# Matrix.net
KiCad netlist of a schematic drawn in Altium Designer
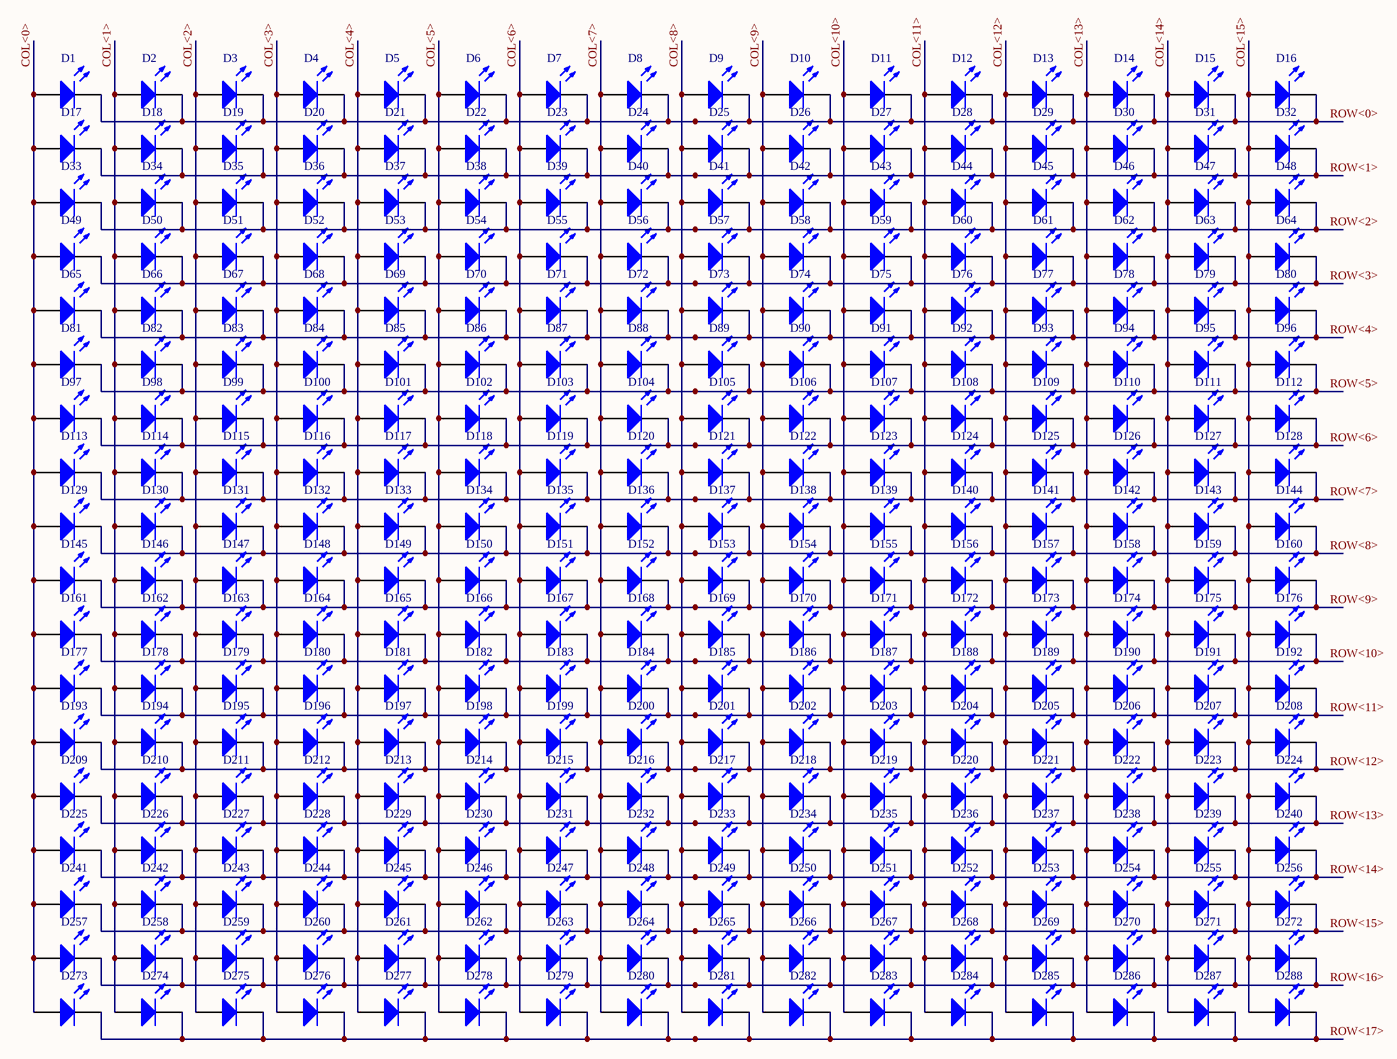
[diagram p0: Matrix.SchDoc]

(export (version "E")
  (design (tool "Eeschema 10.0.6"))
  (components
    (comp (ref "D1")
      (value "~")
      (footprint "LED-UPRIGHT")
      (description "Typical INFRARED GaAs LED")
      (fields (field (name "MANUFACTURER") "Generic Components") (field (name "PUBLISHER") "Altium Limited"))
      (libsource (lib "Miscellaneous Devices") (part "LED0"))
    )
    (comp (ref "D2")
      (value "~")
      (footprint "LED-UPRIGHT")
      (description "Typical INFRARED GaAs LED")
      (fields (field (name "MANUFACTURER") "Generic Components") (field (name "PUBLISHER") "Altium Limited"))
      (libsource (lib "Miscellaneous Devices") (part "LED0"))
    )
    (comp (ref "D3")
      (value "~")
      (footprint "LED-UPRIGHT")
      (description "Typical INFRARED GaAs LED")
      (fields (field (name "MANUFACTURER") "Generic Components") (field (name "PUBLISHER") "Altium Limited"))
      (libsource (lib "Miscellaneous Devices") (part "LED0"))
    )
    (comp (ref "D4")
      (value "~")
      (footprint "LED-UPRIGHT")
      (description "Typical INFRARED GaAs LED")
      (fields (field (name "MANUFACTURER") "Generic Components") (field (name "PUBLISHER") "Altium Limited"))
      (libsource (lib "Miscellaneous Devices") (part "LED0"))
    )
    (comp (ref "D5")
      (value "~")
      (footprint "LED-UPRIGHT")
      (description "Typical INFRARED GaAs LED")
      (fields (field (name "MANUFACTURER") "Generic Components") (field (name "PUBLISHER") "Altium Limited"))
      (libsource (lib "Miscellaneous Devices") (part "LED0"))
    )
    (comp (ref "D6")
      (value "~")
      (footprint "LED-UPRIGHT")
      (description "Typical INFRARED GaAs LED")
      (fields (field (name "MANUFACTURER") "Generic Components") (field (name "PUBLISHER") "Altium Limited"))
      (libsource (lib "Miscellaneous Devices") (part "LED0"))
    )
    (comp (ref "D7")
      (value "~")
      (footprint "LED-UPRIGHT")
      (description "Typical INFRARED GaAs LED")
      (fields (field (name "MANUFACTURER") "Generic Components") (field (name "PUBLISHER") "Altium Limited"))
      (libsource (lib "Miscellaneous Devices") (part "LED0"))
    )
    (comp (ref "D8")
      (value "~")
      (footprint "LED-UPRIGHT")
      (description "Typical INFRARED GaAs LED")
      (fields (field (name "MANUFACTURER") "Generic Components") (field (name "PUBLISHER") "Altium Limited"))
      (libsource (lib "Miscellaneous Devices") (part "LED0"))
    )
    (comp (ref "D9")
      (value "~")
      (footprint "LED-UPRIGHT")
      (description "Typical INFRARED GaAs LED")
      (fields (field (name "MANUFACTURER") "Generic Components") (field (name "PUBLISHER") "Altium Limited"))
      (libsource (lib "Miscellaneous Devices") (part "LED0"))
    )
    (comp (ref "D10")
      (value "~")
      (footprint "LED-UPRIGHT")
      (description "Typical INFRARED GaAs LED")
      (fields (field (name "MANUFACTURER") "Generic Components") (field (name "PUBLISHER") "Altium Limited"))
      (libsource (lib "Miscellaneous Devices") (part "LED0"))
    )
    (comp (ref "D11")
      (value "~")
      (footprint "LED-UPRIGHT")
      (description "Typical INFRARED GaAs LED")
      (fields (field (name "MANUFACTURER") "Generic Components") (field (name "PUBLISHER") "Altium Limited"))
      (libsource (lib "Miscellaneous Devices") (part "LED0"))
    )
    (comp (ref "D12")
      (value "~")
      (footprint "LED-UPRIGHT")
      (description "Typical INFRARED GaAs LED")
      (fields (field (name "MANUFACTURER") "Generic Components") (field (name "PUBLISHER") "Altium Limited"))
      (libsource (lib "Miscellaneous Devices") (part "LED0"))
    )
    (comp (ref "D13")
      (value "~")
      (footprint "LED-UPRIGHT")
      (description "Typical INFRARED GaAs LED")
      (fields (field (name "MANUFACTURER") "Generic Components") (field (name "PUBLISHER") "Altium Limited"))
      (libsource (lib "Miscellaneous Devices") (part "LED0"))
    )
    (comp (ref "D14")
      (value "~")
      (footprint "LED-UPRIGHT")
      (description "Typical INFRARED GaAs LED")
      (fields (field (name "MANUFACTURER") "Generic Components") (field (name "PUBLISHER") "Altium Limited"))
      (libsource (lib "Miscellaneous Devices") (part "LED0"))
    )
    (comp (ref "D15")
      (value "~")
      (footprint "LED-UPRIGHT")
      (description "Typical INFRARED GaAs LED")
      (fields (field (name "MANUFACTURER") "Generic Components") (field (name "PUBLISHER") "Altium Limited"))
      (libsource (lib "Miscellaneous Devices") (part "LED0"))
    )
    (comp (ref "D16")
      (value "~")
      (footprint "LED-UPRIGHT")
      (description "Typical INFRARED GaAs LED")
      (fields (field (name "MANUFACTURER") "Generic Components") (field (name "PUBLISHER") "Altium Limited"))
      (libsource (lib "Miscellaneous Devices") (part "LED0"))
    )
    (comp (ref "D17")
      (value "~")
      (footprint "LED-UPRIGHT")
      (description "Typical INFRARED GaAs LED")
      (fields (field (name "MANUFACTURER") "Generic Components") (field (name "PUBLISHER") "Altium Limited"))
      (libsource (lib "Miscellaneous Devices") (part "LED0"))
    )
    (comp (ref "D18")
      (value "~")
      (footprint "LED-UPRIGHT")
      (description "Typical INFRARED GaAs LED")
      (fields (field (name "MANUFACTURER") "Generic Components") (field (name "PUBLISHER") "Altium Limited"))
      (libsource (lib "Miscellaneous Devices") (part "LED0"))
    )
    (comp (ref "D19")
      (value "~")
      (footprint "LED-UPRIGHT")
      (description "Typical INFRARED GaAs LED")
      (fields (field (name "MANUFACTURER") "Generic Components") (field (name "PUBLISHER") "Altium Limited"))
      (libsource (lib "Miscellaneous Devices") (part "LED0"))
    )
    (comp (ref "D20")
      (value "~")
      (footprint "LED-UPRIGHT")
      (description "Typical INFRARED GaAs LED")
      (fields (field (name "MANUFACTURER") "Generic Components") (field (name "PUBLISHER") "Altium Limited"))
      (libsource (lib "Miscellaneous Devices") (part "LED0"))
    )
    (comp (ref "D21")
      (value "~")
      (footprint "LED-UPRIGHT")
      (description "Typical INFRARED GaAs LED")
      (fields (field (name "MANUFACTURER") "Generic Components") (field (name "PUBLISHER") "Altium Limited"))
      (libsource (lib "Miscellaneous Devices") (part "LED0"))
    )
    (comp (ref "D22")
      (value "~")
      (footprint "LED-UPRIGHT")
      (description "Typical INFRARED GaAs LED")
      (fields (field (name "MANUFACTURER") "Generic Components") (field (name "PUBLISHER") "Altium Limited"))
      (libsource (lib "Miscellaneous Devices") (part "LED0"))
    )
    (comp (ref "D23")
      (value "~")
      (footprint "LED-UPRIGHT")
      (description "Typical INFRARED GaAs LED")
      (fields (field (name "MANUFACTURER") "Generic Components") (field (name "PUBLISHER") "Altium Limited"))
      (libsource (lib "Miscellaneous Devices") (part "LED0"))
    )
    (comp (ref "D24")
      (value "~")
      (footprint "LED-UPRIGHT")
      (description "Typical INFRARED GaAs LED")
      (fields (field (name "MANUFACTURER") "Generic Components") (field (name "PUBLISHER") "Altium Limited"))
      (libsource (lib "Miscellaneous Devices") (part "LED0"))
    )
    (comp (ref "D25")
      (value "~")
      (footprint "LED-UPRIGHT")
      (description "Typical INFRARED GaAs LED")
      (fields (field (name "MANUFACTURER") "Generic Components") (field (name "PUBLISHER") "Altium Limited"))
      (libsource (lib "Miscellaneous Devices") (part "LED0"))
    )
    (comp (ref "D26")
      (value "~")
      (footprint "LED-UPRIGHT")
      (description "Typical INFRARED GaAs LED")
      (fields (field (name "MANUFACTURER") "Generic Components") (field (name "PUBLISHER") "Altium Limited"))
      (libsource (lib "Miscellaneous Devices") (part "LED0"))
    )
    (comp (ref "D27")
      (value "~")
      (footprint "LED-UPRIGHT")
      (description "Typical INFRARED GaAs LED")
      (fields (field (name "MANUFACTURER") "Generic Components") (field (name "PUBLISHER") "Altium Limited"))
      (libsource (lib "Miscellaneous Devices") (part "LED0"))
    )
    (comp (ref "D28")
      (value "~")
      (footprint "LED-UPRIGHT")
      (description "Typical INFRARED GaAs LED")
      (fields (field (name "MANUFACTURER") "Generic Components") (field (name "PUBLISHER") "Altium Limited"))
      (libsource (lib "Miscellaneous Devices") (part "LED0"))
    )
    (comp (ref "D29")
      (value "~")
      (footprint "LED-UPRIGHT")
      (description "Typical INFRARED GaAs LED")
      (fields (field (name "MANUFACTURER") "Generic Components") (field (name "PUBLISHER") "Altium Limited"))
      (libsource (lib "Miscellaneous Devices") (part "LED0"))
    )
    (comp (ref "D30")
      (value "~")
      (footprint "LED-UPRIGHT")
      (description "Typical INFRARED GaAs LED")
      (fields (field (name "MANUFACTURER") "Generic Components") (field (name "PUBLISHER") "Altium Limited"))
      (libsource (lib "Miscellaneous Devices") (part "LED0"))
    )
    (comp (ref "D31")
      (value "~")
      (footprint "LED-UPRIGHT")
      (description "Typical INFRARED GaAs LED")
      (fields (field (name "MANUFACTURER") "Generic Components") (field (name "PUBLISHER") "Altium Limited"))
      (libsource (lib "Miscellaneous Devices") (part "LED0"))
    )
    (comp (ref "D32")
      (value "~")
      (footprint "LED-UPRIGHT")
      (description "Typical INFRARED GaAs LED")
      (fields (field (name "MANUFACTURER") "Generic Components") (field (name "PUBLISHER") "Altium Limited"))
      (libsource (lib "Miscellaneous Devices") (part "LED0"))
    )
    (comp (ref "D33")
      (value "~")
      (footprint "LED-UPRIGHT")
      (description "Typical INFRARED GaAs LED")
      (fields (field (name "MANUFACTURER") "Generic Components") (field (name "PUBLISHER") "Altium Limited"))
      (libsource (lib "Miscellaneous Devices") (part "LED0"))
    )
    (comp (ref "D34")
      (value "~")
      (footprint "LED-UPRIGHT")
      (description "Typical INFRARED GaAs LED")
      (fields (field (name "MANUFACTURER") "Generic Components") (field (name "PUBLISHER") "Altium Limited"))
      (libsource (lib "Miscellaneous Devices") (part "LED0"))
    )
    (comp (ref "D35")
      (value "~")
      (footprint "LED-UPRIGHT")
      (description "Typical INFRARED GaAs LED")
      (fields (field (name "MANUFACTURER") "Generic Components") (field (name "PUBLISHER") "Altium Limited"))
      (libsource (lib "Miscellaneous Devices") (part "LED0"))
    )
    (comp (ref "D36")
      (value "~")
      (footprint "LED-UPRIGHT")
      (description "Typical INFRARED GaAs LED")
      (fields (field (name "MANUFACTURER") "Generic Components") (field (name "PUBLISHER") "Altium Limited"))
      (libsource (lib "Miscellaneous Devices") (part "LED0"))
    )
    (comp (ref "D37")
      (value "~")
      (footprint "LED-UPRIGHT")
      (description "Typical INFRARED GaAs LED")
      (fields (field (name "MANUFACTURER") "Generic Components") (field (name "PUBLISHER") "Altium Limited"))
      (libsource (lib "Miscellaneous Devices") (part "LED0"))
    )
    (comp (ref "D38")
      (value "~")
      (footprint "LED-UPRIGHT")
      (description "Typical INFRARED GaAs LED")
      (fields (field (name "MANUFACTURER") "Generic Components") (field (name "PUBLISHER") "Altium Limited"))
      (libsource (lib "Miscellaneous Devices") (part "LED0"))
    )
    (comp (ref "D39")
      (value "~")
      (footprint "LED-UPRIGHT")
      (description "Typical INFRARED GaAs LED")
      (fields (field (name "MANUFACTURER") "Generic Components") (field (name "PUBLISHER") "Altium Limited"))
      (libsource (lib "Miscellaneous Devices") (part "LED0"))
    )
    (comp (ref "D40")
      (value "~")
      (footprint "LED-UPRIGHT")
      (description "Typical INFRARED GaAs LED")
      (fields (field (name "MANUFACTURER") "Generic Components") (field (name "PUBLISHER") "Altium Limited"))
      (libsource (lib "Miscellaneous Devices") (part "LED0"))
    )
    (comp (ref "D41")
      (value "~")
      (footprint "LED-UPRIGHT")
      (description "Typical INFRARED GaAs LED")
      (fields (field (name "MANUFACTURER") "Generic Components") (field (name "PUBLISHER") "Altium Limited"))
      (libsource (lib "Miscellaneous Devices") (part "LED0"))
    )
    (comp (ref "D42")
      (value "~")
      (footprint "LED-UPRIGHT")
      (description "Typical INFRARED GaAs LED")
      (fields (field (name "MANUFACTURER") "Generic Components") (field (name "PUBLISHER") "Altium Limited"))
      (libsource (lib "Miscellaneous Devices") (part "LED0"))
    )
    (comp (ref "D43")
      (value "~")
      (footprint "LED-UPRIGHT")
      (description "Typical INFRARED GaAs LED")
      (fields (field (name "MANUFACTURER") "Generic Components") (field (name "PUBLISHER") "Altium Limited"))
      (libsource (lib "Miscellaneous Devices") (part "LED0"))
    )
    (comp (ref "D44")
      (value "~")
      (footprint "LED-UPRIGHT")
      (description "Typical INFRARED GaAs LED")
      (fields (field (name "MANUFACTURER") "Generic Components") (field (name "PUBLISHER") "Altium Limited"))
      (libsource (lib "Miscellaneous Devices") (part "LED0"))
    )
    (comp (ref "D45")
      (value "~")
      (footprint "LED-UPRIGHT")
      (description "Typical INFRARED GaAs LED")
      (fields (field (name "MANUFACTURER") "Generic Components") (field (name "PUBLISHER") "Altium Limited"))
      (libsource (lib "Miscellaneous Devices") (part "LED0"))
    )
    (comp (ref "D46")
      (value "~")
      (footprint "LED-UPRIGHT")
      (description "Typical INFRARED GaAs LED")
      (fields (field (name "MANUFACTURER") "Generic Components") (field (name "PUBLISHER") "Altium Limited"))
      (libsource (lib "Miscellaneous Devices") (part "LED0"))
    )
    (comp (ref "D47")
      (value "~")
      (footprint "LED-UPRIGHT")
      (description "Typical INFRARED GaAs LED")
      (fields (field (name "MANUFACTURER") "Generic Components") (field (name "PUBLISHER") "Altium Limited"))
      (libsource (lib "Miscellaneous Devices") (part "LED0"))
    )
    (comp (ref "D48")
      (value "~")
      (footprint "LED-UPRIGHT")
      (description "Typical INFRARED GaAs LED")
      (fields (field (name "MANUFACTURER") "Generic Components") (field (name "PUBLISHER") "Altium Limited"))
      (libsource (lib "Miscellaneous Devices") (part "LED0"))
    )
    (comp (ref "D49")
      (value "~")
      (footprint "LED-UPRIGHT")
      (description "Typical INFRARED GaAs LED")
      (fields (field (name "MANUFACTURER") "Generic Components") (field (name "PUBLISHER") "Altium Limited"))
      (libsource (lib "Miscellaneous Devices") (part "LED0"))
    )
    (comp (ref "D50")
      (value "~")
      (footprint "LED-UPRIGHT")
      (description "Typical INFRARED GaAs LED")
      (fields (field (name "MANUFACTURER") "Generic Components") (field (name "PUBLISHER") "Altium Limited"))
      (libsource (lib "Miscellaneous Devices") (part "LED0"))
    )
    (comp (ref "D51")
      (value "~")
      (footprint "LED-UPRIGHT")
      (description "Typical INFRARED GaAs LED")
      (fields (field (name "MANUFACTURER") "Generic Components") (field (name "PUBLISHER") "Altium Limited"))
      (libsource (lib "Miscellaneous Devices") (part "LED0"))
    )
    (comp (ref "D52")
      (value "~")
      (footprint "LED-UPRIGHT")
      (description "Typical INFRARED GaAs LED")
      (fields (field (name "MANUFACTURER") "Generic Components") (field (name "PUBLISHER") "Altium Limited"))
      (libsource (lib "Miscellaneous Devices") (part "LED0"))
    )
    (comp (ref "D53")
      (value "~")
      (footprint "LED-UPRIGHT")
      (description "Typical INFRARED GaAs LED")
      (fields (field (name "MANUFACTURER") "Generic Components") (field (name "PUBLISHER") "Altium Limited"))
      (libsource (lib "Miscellaneous Devices") (part "LED0"))
    )
    (comp (ref "D54")
      (value "~")
      (footprint "LED-UPRIGHT")
      (description "Typical INFRARED GaAs LED")
      (fields (field (name "MANUFACTURER") "Generic Components") (field (name "PUBLISHER") "Altium Limited"))
      (libsource (lib "Miscellaneous Devices") (part "LED0"))
    )
    (comp (ref "D55")
      (value "~")
      (footprint "LED-UPRIGHT")
      (description "Typical INFRARED GaAs LED")
      (fields (field (name "MANUFACTURER") "Generic Components") (field (name "PUBLISHER") "Altium Limited"))
      (libsource (lib "Miscellaneous Devices") (part "LED0"))
    )
    (comp (ref "D56")
      (value "~")
      (footprint "LED-UPRIGHT")
      (description "Typical INFRARED GaAs LED")
      (fields (field (name "MANUFACTURER") "Generic Components") (field (name "PUBLISHER") "Altium Limited"))
      (libsource (lib "Miscellaneous Devices") (part "LED0"))
    )
    (comp (ref "D57")
      (value "~")
      (footprint "LED-UPRIGHT")
      (description "Typical INFRARED GaAs LED")
      (fields (field (name "MANUFACTURER") "Generic Components") (field (name "PUBLISHER") "Altium Limited"))
      (libsource (lib "Miscellaneous Devices") (part "LED0"))
    )
    (comp (ref "D58")
      (value "~")
      (footprint "LED-UPRIGHT")
      (description "Typical INFRARED GaAs LED")
      (fields (field (name "MANUFACTURER") "Generic Components") (field (name "PUBLISHER") "Altium Limited"))
      (libsource (lib "Miscellaneous Devices") (part "LED0"))
    )
    (comp (ref "D59")
      (value "~")
      (footprint "LED-UPRIGHT")
      (description "Typical INFRARED GaAs LED")
      (fields (field (name "MANUFACTURER") "Generic Components") (field (name "PUBLISHER") "Altium Limited"))
      (libsource (lib "Miscellaneous Devices") (part "LED0"))
    )
    (comp (ref "D60")
      (value "~")
      (footprint "LED-UPRIGHT")
      (description "Typical INFRARED GaAs LED")
      (fields (field (name "MANUFACTURER") "Generic Components") (field (name "PUBLISHER") "Altium Limited"))
      (libsource (lib "Miscellaneous Devices") (part "LED0"))
    )
    (comp (ref "D61")
      (value "~")
      (footprint "LED-UPRIGHT")
      (description "Typical INFRARED GaAs LED")
      (fields (field (name "MANUFACTURER") "Generic Components") (field (name "PUBLISHER") "Altium Limited"))
      (libsource (lib "Miscellaneous Devices") (part "LED0"))
    )
    (comp (ref "D62")
      (value "~")
      (footprint "LED-UPRIGHT")
      (description "Typical INFRARED GaAs LED")
      (fields (field (name "MANUFACTURER") "Generic Components") (field (name "PUBLISHER") "Altium Limited"))
      (libsource (lib "Miscellaneous Devices") (part "LED0"))
    )
    (comp (ref "D63")
      (value "~")
      (footprint "LED-UPRIGHT")
      (description "Typical INFRARED GaAs LED")
      (fields (field (name "MANUFACTURER") "Generic Components") (field (name "PUBLISHER") "Altium Limited"))
      (libsource (lib "Miscellaneous Devices") (part "LED0"))
    )
    (comp (ref "D64")
      (value "~")
      (footprint "LED-UPRIGHT")
      (description "Typical INFRARED GaAs LED")
      (fields (field (name "MANUFACTURER") "Generic Components") (field (name "PUBLISHER") "Altium Limited"))
      (libsource (lib "Miscellaneous Devices") (part "LED0"))
    )
    (comp (ref "D65")
      (value "~")
      (footprint "LED-UPRIGHT")
      (description "Typical INFRARED GaAs LED")
      (fields (field (name "MANUFACTURER") "Generic Components") (field (name "PUBLISHER") "Altium Limited"))
      (libsource (lib "Miscellaneous Devices") (part "LED0"))
    )
    (comp (ref "D66")
      (value "~")
      (footprint "LED-UPRIGHT")
      (description "Typical INFRARED GaAs LED")
      (fields (field (name "MANUFACTURER") "Generic Components") (field (name "PUBLISHER") "Altium Limited"))
      (libsource (lib "Miscellaneous Devices") (part "LED0"))
    )
    (comp (ref "D67")
      (value "~")
      (footprint "LED-UPRIGHT")
      (description "Typical INFRARED GaAs LED")
      (fields (field (name "MANUFACTURER") "Generic Components") (field (name "PUBLISHER") "Altium Limited"))
      (libsource (lib "Miscellaneous Devices") (part "LED0"))
    )
    (comp (ref "D68")
      (value "~")
      (footprint "LED-UPRIGHT")
      (description "Typical INFRARED GaAs LED")
      (fields (field (name "MANUFACTURER") "Generic Components") (field (name "PUBLISHER") "Altium Limited"))
      (libsource (lib "Miscellaneous Devices") (part "LED0"))
    )
    (comp (ref "D69")
      (value "~")
      (footprint "LED-UPRIGHT")
      (description "Typical INFRARED GaAs LED")
      (fields (field (name "MANUFACTURER") "Generic Components") (field (name "PUBLISHER") "Altium Limited"))
      (libsource (lib "Miscellaneous Devices") (part "LED0"))
    )
    (comp (ref "D70")
      (value "~")
      (footprint "LED-UPRIGHT")
      (description "Typical INFRARED GaAs LED")
      (fields (field (name "MANUFACTURER") "Generic Components") (field (name "PUBLISHER") "Altium Limited"))
      (libsource (lib "Miscellaneous Devices") (part "LED0"))
    )
    (comp (ref "D71")
      (value "~")
      (footprint "LED-UPRIGHT")
      (description "Typical INFRARED GaAs LED")
      (fields (field (name "MANUFACTURER") "Generic Components") (field (name "PUBLISHER") "Altium Limited"))
      (libsource (lib "Miscellaneous Devices") (part "LED0"))
    )
    (comp (ref "D72")
      (value "~")
      (footprint "LED-UPRIGHT")
      (description "Typical INFRARED GaAs LED")
      (fields (field (name "MANUFACTURER") "Generic Components") (field (name "PUBLISHER") "Altium Limited"))
      (libsource (lib "Miscellaneous Devices") (part "LED0"))
    )
    (comp (ref "D73")
      (value "~")
      (footprint "LED-UPRIGHT")
      (description "Typical INFRARED GaAs LED")
      (fields (field (name "MANUFACTURER") "Generic Components") (field (name "PUBLISHER") "Altium Limited"))
      (libsource (lib "Miscellaneous Devices") (part "LED0"))
    )
    (comp (ref "D74")
      (value "~")
      (footprint "LED-UPRIGHT")
      (description "Typical INFRARED GaAs LED")
      (fields (field (name "MANUFACTURER") "Generic Components") (field (name "PUBLISHER") "Altium Limited"))
      (libsource (lib "Miscellaneous Devices") (part "LED0"))
    )
    (comp (ref "D75")
      (value "~")
      (footprint "LED-UPRIGHT")
      (description "Typical INFRARED GaAs LED")
      (fields (field (name "MANUFACTURER") "Generic Components") (field (name "PUBLISHER") "Altium Limited"))
      (libsource (lib "Miscellaneous Devices") (part "LED0"))
    )
    (comp (ref "D76")
      (value "~")
      (footprint "LED-UPRIGHT")
      (description "Typical INFRARED GaAs LED")
      (fields (field (name "MANUFACTURER") "Generic Components") (field (name "PUBLISHER") "Altium Limited"))
      (libsource (lib "Miscellaneous Devices") (part "LED0"))
    )
    (comp (ref "D77")
      (value "~")
      (footprint "LED-UPRIGHT")
      (description "Typical INFRARED GaAs LED")
      (fields (field (name "MANUFACTURER") "Generic Components") (field (name "PUBLISHER") "Altium Limited"))
      (libsource (lib "Miscellaneous Devices") (part "LED0"))
    )
    (comp (ref "D78")
      (value "~")
      (footprint "LED-UPRIGHT")
      (description "Typical INFRARED GaAs LED")
      (fields (field (name "MANUFACTURER") "Generic Components") (field (name "PUBLISHER") "Altium Limited"))
      (libsource (lib "Miscellaneous Devices") (part "LED0"))
    )
    (comp (ref "D79")
      (value "~")
      (footprint "LED-UPRIGHT")
      (description "Typical INFRARED GaAs LED")
      (fields (field (name "MANUFACTURER") "Generic Components") (field (name "PUBLISHER") "Altium Limited"))
      (libsource (lib "Miscellaneous Devices") (part "LED0"))
    )
    (comp (ref "D80")
      (value "~")
      (footprint "LED-UPRIGHT")
      (description "Typical INFRARED GaAs LED")
      (fields (field (name "MANUFACTURER") "Generic Components") (field (name "PUBLISHER") "Altium Limited"))
      (libsource (lib "Miscellaneous Devices") (part "LED0"))
    )
    (comp (ref "D81")
      (value "~")
      (footprint "LED-UPRIGHT")
      (description "Typical INFRARED GaAs LED")
      (fields (field (name "MANUFACTURER") "Generic Components") (field (name "PUBLISHER") "Altium Limited"))
      (libsource (lib "Miscellaneous Devices") (part "LED0"))
    )
    (comp (ref "D82")
      (value "~")
      (footprint "LED-UPRIGHT")
      (description "Typical INFRARED GaAs LED")
      (fields (field (name "MANUFACTURER") "Generic Components") (field (name "PUBLISHER") "Altium Limited"))
      (libsource (lib "Miscellaneous Devices") (part "LED0"))
    )
    (comp (ref "D83")
      (value "~")
      (footprint "LED-UPRIGHT")
      (description "Typical INFRARED GaAs LED")
      (fields (field (name "MANUFACTURER") "Generic Components") (field (name "PUBLISHER") "Altium Limited"))
      (libsource (lib "Miscellaneous Devices") (part "LED0"))
    )
    (comp (ref "D84")
      (value "~")
      (footprint "LED-UPRIGHT")
      (description "Typical INFRARED GaAs LED")
      (fields (field (name "MANUFACTURER") "Generic Components") (field (name "PUBLISHER") "Altium Limited"))
      (libsource (lib "Miscellaneous Devices") (part "LED0"))
    )
    (comp (ref "D85")
      (value "~")
      (footprint "LED-UPRIGHT")
      (description "Typical INFRARED GaAs LED")
      (fields (field (name "MANUFACTURER") "Generic Components") (field (name "PUBLISHER") "Altium Limited"))
      (libsource (lib "Miscellaneous Devices") (part "LED0"))
    )
    (comp (ref "D86")
      (value "~")
      (footprint "LED-UPRIGHT")
      (description "Typical INFRARED GaAs LED")
      (fields (field (name "MANUFACTURER") "Generic Components") (field (name "PUBLISHER") "Altium Limited"))
      (libsource (lib "Miscellaneous Devices") (part "LED0"))
    )
    (comp (ref "D87")
      (value "~")
      (footprint "LED-UPRIGHT")
      (description "Typical INFRARED GaAs LED")
      (fields (field (name "MANUFACTURER") "Generic Components") (field (name "PUBLISHER") "Altium Limited"))
      (libsource (lib "Miscellaneous Devices") (part "LED0"))
    )
    (comp (ref "D88")
      (value "~")
      (footprint "LED-UPRIGHT")
      (description "Typical INFRARED GaAs LED")
      (fields (field (name "MANUFACTURER") "Generic Components") (field (name "PUBLISHER") "Altium Limited"))
      (libsource (lib "Miscellaneous Devices") (part "LED0"))
    )
    (comp (ref "D89")
      (value "~")
      (footprint "LED-UPRIGHT")
      (description "Typical INFRARED GaAs LED")
      (fields (field (name "MANUFACTURER") "Generic Components") (field (name "PUBLISHER") "Altium Limited"))
      (libsource (lib "Miscellaneous Devices") (part "LED0"))
    )
    (comp (ref "D90")
      (value "~")
      (footprint "LED-UPRIGHT")
      (description "Typical INFRARED GaAs LED")
      (fields (field (name "MANUFACTURER") "Generic Components") (field (name "PUBLISHER") "Altium Limited"))
      (libsource (lib "Miscellaneous Devices") (part "LED0"))
    )
    (comp (ref "D91")
      (value "~")
      (footprint "LED-UPRIGHT")
      (description "Typical INFRARED GaAs LED")
      (fields (field (name "MANUFACTURER") "Generic Components") (field (name "PUBLISHER") "Altium Limited"))
      (libsource (lib "Miscellaneous Devices") (part "LED0"))
    )
    (comp (ref "D92")
      (value "~")
      (footprint "LED-UPRIGHT")
      (description "Typical INFRARED GaAs LED")
      (fields (field (name "MANUFACTURER") "Generic Components") (field (name "PUBLISHER") "Altium Limited"))
      (libsource (lib "Miscellaneous Devices") (part "LED0"))
    )
    (comp (ref "D93")
      (value "~")
      (footprint "LED-UPRIGHT")
      (description "Typical INFRARED GaAs LED")
      (fields (field (name "MANUFACTURER") "Generic Components") (field (name "PUBLISHER") "Altium Limited"))
      (libsource (lib "Miscellaneous Devices") (part "LED0"))
    )
    (comp (ref "D94")
      (value "~")
      (footprint "LED-UPRIGHT")
      (description "Typical INFRARED GaAs LED")
      (fields (field (name "MANUFACTURER") "Generic Components") (field (name "PUBLISHER") "Altium Limited"))
      (libsource (lib "Miscellaneous Devices") (part "LED0"))
    )
    (comp (ref "D95")
      (value "~")
      (footprint "LED-UPRIGHT")
      (description "Typical INFRARED GaAs LED")
      (fields (field (name "MANUFACTURER") "Generic Components") (field (name "PUBLISHER") "Altium Limited"))
      (libsource (lib "Miscellaneous Devices") (part "LED0"))
    )
    (comp (ref "D96")
      (value "~")
      (footprint "LED-UPRIGHT")
      (description "Typical INFRARED GaAs LED")
      (fields (field (name "MANUFACTURER") "Generic Components") (field (name "PUBLISHER") "Altium Limited"))
      (libsource (lib "Miscellaneous Devices") (part "LED0"))
    )
    (comp (ref "D97")
      (value "~")
      (footprint "LED-UPRIGHT")
      (description "Typical INFRARED GaAs LED")
      (fields (field (name "MANUFACTURER") "Generic Components") (field (name "PUBLISHER") "Altium Limited"))
      (libsource (lib "Miscellaneous Devices") (part "LED0"))
    )
    (comp (ref "D98")
      (value "~")
      (footprint "LED-UPRIGHT")
      (description "Typical INFRARED GaAs LED")
      (fields (field (name "MANUFACTURER") "Generic Components") (field (name "PUBLISHER") "Altium Limited"))
      (libsource (lib "Miscellaneous Devices") (part "LED0"))
    )
    (comp (ref "D99")
      (value "~")
      (footprint "LED-UPRIGHT")
      (description "Typical INFRARED GaAs LED")
      (fields (field (name "MANUFACTURER") "Generic Components") (field (name "PUBLISHER") "Altium Limited"))
      (libsource (lib "Miscellaneous Devices") (part "LED0"))
    )
    (comp (ref "D100")
      (value "~")
      (footprint "LED-UPRIGHT")
      (description "Typical INFRARED GaAs LED")
      (fields (field (name "MANUFACTURER") "Generic Components") (field (name "PUBLISHER") "Altium Limited"))
      (libsource (lib "Miscellaneous Devices") (part "LED0"))
    )
    (comp (ref "D101")
      (value "~")
      (footprint "LED-UPRIGHT")
      (description "Typical INFRARED GaAs LED")
      (fields (field (name "MANUFACTURER") "Generic Components") (field (name "PUBLISHER") "Altium Limited"))
      (libsource (lib "Miscellaneous Devices") (part "LED0"))
    )
    (comp (ref "D102")
      (value "~")
      (footprint "LED-UPRIGHT")
      (description "Typical INFRARED GaAs LED")
      (fields (field (name "MANUFACTURER") "Generic Components") (field (name "PUBLISHER") "Altium Limited"))
      (libsource (lib "Miscellaneous Devices") (part "LED0"))
    )
    (comp (ref "D103")
      (value "~")
      (footprint "LED-UPRIGHT")
      (description "Typical INFRARED GaAs LED")
      (fields (field (name "MANUFACTURER") "Generic Components") (field (name "PUBLISHER") "Altium Limited"))
      (libsource (lib "Miscellaneous Devices") (part "LED0"))
    )
    (comp (ref "D104")
      (value "~")
      (footprint "LED-UPRIGHT")
      (description "Typical INFRARED GaAs LED")
      (fields (field (name "MANUFACTURER") "Generic Components") (field (name "PUBLISHER") "Altium Limited"))
      (libsource (lib "Miscellaneous Devices") (part "LED0"))
    )
    (comp (ref "D105")
      (value "~")
      (footprint "LED-UPRIGHT")
      (description "Typical INFRARED GaAs LED")
      (fields (field (name "MANUFACTURER") "Generic Components") (field (name "PUBLISHER") "Altium Limited"))
      (libsource (lib "Miscellaneous Devices") (part "LED0"))
    )
    (comp (ref "D106")
      (value "~")
      (footprint "LED-UPRIGHT")
      (description "Typical INFRARED GaAs LED")
      (fields (field (name "MANUFACTURER") "Generic Components") (field (name "PUBLISHER") "Altium Limited"))
      (libsource (lib "Miscellaneous Devices") (part "LED0"))
    )
    (comp (ref "D107")
      (value "~")
      (footprint "LED-UPRIGHT")
      (description "Typical INFRARED GaAs LED")
      (fields (field (name "MANUFACTURER") "Generic Components") (field (name "PUBLISHER") "Altium Limited"))
      (libsource (lib "Miscellaneous Devices") (part "LED0"))
    )
    (comp (ref "D108")
      (value "~")
      (footprint "LED-UPRIGHT")
      (description "Typical INFRARED GaAs LED")
      (fields (field (name "MANUFACTURER") "Generic Components") (field (name "PUBLISHER") "Altium Limited"))
      (libsource (lib "Miscellaneous Devices") (part "LED0"))
    )
    (comp (ref "D109")
      (value "~")
      (footprint "LED-UPRIGHT")
      (description "Typical INFRARED GaAs LED")
      (fields (field (name "MANUFACTURER") "Generic Components") (field (name "PUBLISHER") "Altium Limited"))
      (libsource (lib "Miscellaneous Devices") (part "LED0"))
    )
    (comp (ref "D110")
      (value "~")
      (footprint "LED-UPRIGHT")
      (description "Typical INFRARED GaAs LED")
      (fields (field (name "MANUFACTURER") "Generic Components") (field (name "PUBLISHER") "Altium Limited"))
      (libsource (lib "Miscellaneous Devices") (part "LED0"))
    )
    (comp (ref "D111")
      (value "~")
      (footprint "LED-UPRIGHT")
      (description "Typical INFRARED GaAs LED")
      (fields (field (name "MANUFACTURER") "Generic Components") (field (name "PUBLISHER") "Altium Limited"))
      (libsource (lib "Miscellaneous Devices") (part "LED0"))
    )
    (comp (ref "D112")
      (value "~")
      (footprint "LED-UPRIGHT")
      (description "Typical INFRARED GaAs LED")
      (fields (field (name "MANUFACTURER") "Generic Components") (field (name "PUBLISHER") "Altium Limited"))
      (libsource (lib "Miscellaneous Devices") (part "LED0"))
    )
    (comp (ref "D113")
      (value "~")
      (footprint "LED-UPRIGHT")
      (description "Typical INFRARED GaAs LED")
      (fields (field (name "MANUFACTURER") "Generic Components") (field (name "PUBLISHER") "Altium Limited"))
      (libsource (lib "Miscellaneous Devices") (part "LED0"))
    )
    (comp (ref "D114")
      (value "~")
      (footprint "LED-UPRIGHT")
      (description "Typical INFRARED GaAs LED")
      (fields (field (name "MANUFACTURER") "Generic Components") (field (name "PUBLISHER") "Altium Limited"))
      (libsource (lib "Miscellaneous Devices") (part "LED0"))
    )
    (comp (ref "D115")
      (value "~")
      (footprint "LED-UPRIGHT")
      (description "Typical INFRARED GaAs LED")
      (fields (field (name "MANUFACTURER") "Generic Components") (field (name "PUBLISHER") "Altium Limited"))
      (libsource (lib "Miscellaneous Devices") (part "LED0"))
    )
    (comp (ref "D116")
      (value "~")
      (footprint "LED-UPRIGHT")
      (description "Typical INFRARED GaAs LED")
      (fields (field (name "MANUFACTURER") "Generic Components") (field (name "PUBLISHER") "Altium Limited"))
      (libsource (lib "Miscellaneous Devices") (part "LED0"))
    )
    (comp (ref "D117")
      (value "~")
      (footprint "LED-UPRIGHT")
      (description "Typical INFRARED GaAs LED")
      (fields (field (name "MANUFACTURER") "Generic Components") (field (name "PUBLISHER") "Altium Limited"))
      (libsource (lib "Miscellaneous Devices") (part "LED0"))
    )
    (comp (ref "D118")
      (value "~")
      (footprint "LED-UPRIGHT")
      (description "Typical INFRARED GaAs LED")
      (fields (field (name "MANUFACTURER") "Generic Components") (field (name "PUBLISHER") "Altium Limited"))
      (libsource (lib "Miscellaneous Devices") (part "LED0"))
    )
    (comp (ref "D119")
      (value "~")
      (footprint "LED-UPRIGHT")
      (description "Typical INFRARED GaAs LED")
      (fields (field (name "MANUFACTURER") "Generic Components") (field (name "PUBLISHER") "Altium Limited"))
      (libsource (lib "Miscellaneous Devices") (part "LED0"))
    )
    (comp (ref "D120")
      (value "~")
      (footprint "LED-UPRIGHT")
      (description "Typical INFRARED GaAs LED")
      (fields (field (name "MANUFACTURER") "Generic Components") (field (name "PUBLISHER") "Altium Limited"))
      (libsource (lib "Miscellaneous Devices") (part "LED0"))
    )
    (comp (ref "D121")
      (value "~")
      (footprint "LED-UPRIGHT")
      (description "Typical INFRARED GaAs LED")
      (fields (field (name "MANUFACTURER") "Generic Components") (field (name "PUBLISHER") "Altium Limited"))
      (libsource (lib "Miscellaneous Devices") (part "LED0"))
    )
    (comp (ref "D122")
      (value "~")
      (footprint "LED-UPRIGHT")
      (description "Typical INFRARED GaAs LED")
      (fields (field (name "MANUFACTURER") "Generic Components") (field (name "PUBLISHER") "Altium Limited"))
      (libsource (lib "Miscellaneous Devices") (part "LED0"))
    )
    (comp (ref "D123")
      (value "~")
      (footprint "LED-UPRIGHT")
      (description "Typical INFRARED GaAs LED")
      (fields (field (name "MANUFACTURER") "Generic Components") (field (name "PUBLISHER") "Altium Limited"))
      (libsource (lib "Miscellaneous Devices") (part "LED0"))
    )
    (comp (ref "D124")
      (value "~")
      (footprint "LED-UPRIGHT")
      (description "Typical INFRARED GaAs LED")
      (fields (field (name "MANUFACTURER") "Generic Components") (field (name "PUBLISHER") "Altium Limited"))
      (libsource (lib "Miscellaneous Devices") (part "LED0"))
    )
    (comp (ref "D125")
      (value "~")
      (footprint "LED-UPRIGHT")
      (description "Typical INFRARED GaAs LED")
      (fields (field (name "MANUFACTURER") "Generic Components") (field (name "PUBLISHER") "Altium Limited"))
      (libsource (lib "Miscellaneous Devices") (part "LED0"))
    )
    (comp (ref "D126")
      (value "~")
      (footprint "LED-UPRIGHT")
      (description "Typical INFRARED GaAs LED")
      (fields (field (name "MANUFACTURER") "Generic Components") (field (name "PUBLISHER") "Altium Limited"))
      (libsource (lib "Miscellaneous Devices") (part "LED0"))
    )
    (comp (ref "D127")
      (value "~")
      (footprint "LED-UPRIGHT")
      (description "Typical INFRARED GaAs LED")
      (fields (field (name "MANUFACTURER") "Generic Components") (field (name "PUBLISHER") "Altium Limited"))
      (libsource (lib "Miscellaneous Devices") (part "LED0"))
    )
    (comp (ref "D128")
      (value "~")
      (footprint "LED-UPRIGHT")
      (description "Typical INFRARED GaAs LED")
      (fields (field (name "MANUFACTURER") "Generic Components") (field (name "PUBLISHER") "Altium Limited"))
      (libsource (lib "Miscellaneous Devices") (part "LED0"))
    )
    (comp (ref "D129")
      (value "~")
      (footprint "LED-UPRIGHT")
      (description "Typical INFRARED GaAs LED")
      (fields (field (name "MANUFACTURER") "Generic Components") (field (name "PUBLISHER") "Altium Limited"))
      (libsource (lib "Miscellaneous Devices") (part "LED0"))
    )
    (comp (ref "D130")
      (value "~")
      (footprint "LED-UPRIGHT")
      (description "Typical INFRARED GaAs LED")
      (fields (field (name "MANUFACTURER") "Generic Components") (field (name "PUBLISHER") "Altium Limited"))
      (libsource (lib "Miscellaneous Devices") (part "LED0"))
    )
    (comp (ref "D131")
      (value "~")
      (footprint "LED-UPRIGHT")
      (description "Typical INFRARED GaAs LED")
      (fields (field (name "MANUFACTURER") "Generic Components") (field (name "PUBLISHER") "Altium Limited"))
      (libsource (lib "Miscellaneous Devices") (part "LED0"))
    )
    (comp (ref "D132")
      (value "~")
      (footprint "LED-UPRIGHT")
      (description "Typical INFRARED GaAs LED")
      (fields (field (name "MANUFACTURER") "Generic Components") (field (name "PUBLISHER") "Altium Limited"))
      (libsource (lib "Miscellaneous Devices") (part "LED0"))
    )
    (comp (ref "D133")
      (value "~")
      (footprint "LED-UPRIGHT")
      (description "Typical INFRARED GaAs LED")
      (fields (field (name "MANUFACTURER") "Generic Components") (field (name "PUBLISHER") "Altium Limited"))
      (libsource (lib "Miscellaneous Devices") (part "LED0"))
    )
    (comp (ref "D134")
      (value "~")
      (footprint "LED-UPRIGHT")
      (description "Typical INFRARED GaAs LED")
      (fields (field (name "MANUFACTURER") "Generic Components") (field (name "PUBLISHER") "Altium Limited"))
      (libsource (lib "Miscellaneous Devices") (part "LED0"))
    )
    (comp (ref "D135")
      (value "~")
      (footprint "LED-UPRIGHT")
      (description "Typical INFRARED GaAs LED")
      (fields (field (name "MANUFACTURER") "Generic Components") (field (name "PUBLISHER") "Altium Limited"))
      (libsource (lib "Miscellaneous Devices") (part "LED0"))
    )
    (comp (ref "D136")
      (value "~")
      (footprint "LED-UPRIGHT")
      (description "Typical INFRARED GaAs LED")
      (fields (field (name "MANUFACTURER") "Generic Components") (field (name "PUBLISHER") "Altium Limited"))
      (libsource (lib "Miscellaneous Devices") (part "LED0"))
    )
    (comp (ref "D137")
      (value "~")
      (footprint "LED-UPRIGHT")
      (description "Typical INFRARED GaAs LED")
      (fields (field (name "MANUFACTURER") "Generic Components") (field (name "PUBLISHER") "Altium Limited"))
      (libsource (lib "Miscellaneous Devices") (part "LED0"))
    )
    (comp (ref "D138")
      (value "~")
      (footprint "LED-UPRIGHT")
      (description "Typical INFRARED GaAs LED")
      (fields (field (name "MANUFACTURER") "Generic Components") (field (name "PUBLISHER") "Altium Limited"))
      (libsource (lib "Miscellaneous Devices") (part "LED0"))
    )
    (comp (ref "D139")
      (value "~")
      (footprint "LED-UPRIGHT")
      (description "Typical INFRARED GaAs LED")
      (fields (field (name "MANUFACTURER") "Generic Components") (field (name "PUBLISHER") "Altium Limited"))
      (libsource (lib "Miscellaneous Devices") (part "LED0"))
    )
    (comp (ref "D140")
      (value "~")
      (footprint "LED-UPRIGHT")
      (description "Typical INFRARED GaAs LED")
      (fields (field (name "MANUFACTURER") "Generic Components") (field (name "PUBLISHER") "Altium Limited"))
      (libsource (lib "Miscellaneous Devices") (part "LED0"))
    )
    (comp (ref "D141")
      (value "~")
      (footprint "LED-UPRIGHT")
      (description "Typical INFRARED GaAs LED")
      (fields (field (name "MANUFACTURER") "Generic Components") (field (name "PUBLISHER") "Altium Limited"))
      (libsource (lib "Miscellaneous Devices") (part "LED0"))
    )
    (comp (ref "D142")
      (value "~")
      (footprint "LED-UPRIGHT")
      (description "Typical INFRARED GaAs LED")
      (fields (field (name "MANUFACTURER") "Generic Components") (field (name "PUBLISHER") "Altium Limited"))
      (libsource (lib "Miscellaneous Devices") (part "LED0"))
    )
    (comp (ref "D143")
      (value "~")
      (footprint "LED-UPRIGHT")
      (description "Typical INFRARED GaAs LED")
      (fields (field (name "MANUFACTURER") "Generic Components") (field (name "PUBLISHER") "Altium Limited"))
      (libsource (lib "Miscellaneous Devices") (part "LED0"))
    )
    (comp (ref "D144")
      (value "~")
      (footprint "LED-UPRIGHT")
      (description "Typical INFRARED GaAs LED")
      (fields (field (name "MANUFACTURER") "Generic Components") (field (name "PUBLISHER") "Altium Limited"))
      (libsource (lib "Miscellaneous Devices") (part "LED0"))
    )
    (comp (ref "D145")
      (value "~")
      (footprint "LED-UPRIGHT")
      (description "Typical INFRARED GaAs LED")
      (fields (field (name "MANUFACTURER") "Generic Components") (field (name "PUBLISHER") "Altium Limited"))
      (libsource (lib "Miscellaneous Devices") (part "LED0"))
    )
    (comp (ref "D146")
      (value "~")
      (footprint "LED-UPRIGHT")
      (description "Typical INFRARED GaAs LED")
      (fields (field (name "MANUFACTURER") "Generic Components") (field (name "PUBLISHER") "Altium Limited"))
      (libsource (lib "Miscellaneous Devices") (part "LED0"))
    )
    (comp (ref "D147")
      (value "~")
      (footprint "LED-UPRIGHT")
      (description "Typical INFRARED GaAs LED")
      (fields (field (name "MANUFACTURER") "Generic Components") (field (name "PUBLISHER") "Altium Limited"))
      (libsource (lib "Miscellaneous Devices") (part "LED0"))
    )
    (comp (ref "D148")
      (value "~")
      (footprint "LED-UPRIGHT")
      (description "Typical INFRARED GaAs LED")
      (fields (field (name "MANUFACTURER") "Generic Components") (field (name "PUBLISHER") "Altium Limited"))
      (libsource (lib "Miscellaneous Devices") (part "LED0"))
    )
    (comp (ref "D149")
      (value "~")
      (footprint "LED-UPRIGHT")
      (description "Typical INFRARED GaAs LED")
      (fields (field (name "MANUFACTURER") "Generic Components") (field (name "PUBLISHER") "Altium Limited"))
      (libsource (lib "Miscellaneous Devices") (part "LED0"))
    )
    (comp (ref "D150")
      (value "~")
      (footprint "LED-UPRIGHT")
      (description "Typical INFRARED GaAs LED")
      (fields (field (name "MANUFACTURER") "Generic Components") (field (name "PUBLISHER") "Altium Limited"))
      (libsource (lib "Miscellaneous Devices") (part "LED0"))
    )
    (comp (ref "D151")
      (value "~")
      (footprint "LED-UPRIGHT")
      (description "Typical INFRARED GaAs LED")
      (fields (field (name "MANUFACTURER") "Generic Components") (field (name "PUBLISHER") "Altium Limited"))
      (libsource (lib "Miscellaneous Devices") (part "LED0"))
    )
    (comp (ref "D152")
      (value "~")
      (footprint "LED-UPRIGHT")
      (description "Typical INFRARED GaAs LED")
      (fields (field (name "MANUFACTURER") "Generic Components") (field (name "PUBLISHER") "Altium Limited"))
      (libsource (lib "Miscellaneous Devices") (part "LED0"))
    )
    (comp (ref "D153")
      (value "~")
      (footprint "LED-UPRIGHT")
      (description "Typical INFRARED GaAs LED")
      (fields (field (name "MANUFACTURER") "Generic Components") (field (name "PUBLISHER") "Altium Limited"))
      (libsource (lib "Miscellaneous Devices") (part "LED0"))
    )
    (comp (ref "D154")
      (value "~")
      (footprint "LED-UPRIGHT")
      (description "Typical INFRARED GaAs LED")
      (fields (field (name "MANUFACTURER") "Generic Components") (field (name "PUBLISHER") "Altium Limited"))
      (libsource (lib "Miscellaneous Devices") (part "LED0"))
    )
    (comp (ref "D155")
      (value "~")
      (footprint "LED-UPRIGHT")
      (description "Typical INFRARED GaAs LED")
      (fields (field (name "MANUFACTURER") "Generic Components") (field (name "PUBLISHER") "Altium Limited"))
      (libsource (lib "Miscellaneous Devices") (part "LED0"))
    )
    (comp (ref "D156")
      (value "~")
      (footprint "LED-UPRIGHT")
      (description "Typical INFRARED GaAs LED")
      (fields (field (name "MANUFACTURER") "Generic Components") (field (name "PUBLISHER") "Altium Limited"))
      (libsource (lib "Miscellaneous Devices") (part "LED0"))
    )
    (comp (ref "D157")
      (value "~")
      (footprint "LED-UPRIGHT")
      (description "Typical INFRARED GaAs LED")
      (fields (field (name "MANUFACTURER") "Generic Components") (field (name "PUBLISHER") "Altium Limited"))
      (libsource (lib "Miscellaneous Devices") (part "LED0"))
    )
    (comp (ref "D158")
      (value "~")
      (footprint "LED-UPRIGHT")
      (description "Typical INFRARED GaAs LED")
      (fields (field (name "MANUFACTURER") "Generic Components") (field (name "PUBLISHER") "Altium Limited"))
      (libsource (lib "Miscellaneous Devices") (part "LED0"))
    )
    (comp (ref "D159")
      (value "~")
      (footprint "LED-UPRIGHT")
      (description "Typical INFRARED GaAs LED")
      (fields (field (name "MANUFACTURER") "Generic Components") (field (name "PUBLISHER") "Altium Limited"))
      (libsource (lib "Miscellaneous Devices") (part "LED0"))
    )
    (comp (ref "D160")
      (value "~")
      (footprint "LED-UPRIGHT")
      (description "Typical INFRARED GaAs LED")
      (fields (field (name "MANUFACTURER") "Generic Components") (field (name "PUBLISHER") "Altium Limited"))
      (libsource (lib "Miscellaneous Devices") (part "LED0"))
    )
    (comp (ref "D161")
      (value "~")
      (footprint "LED-UPRIGHT")
      (description "Typical INFRARED GaAs LED")
      (fields (field (name "MANUFACTURER") "Generic Components") (field (name "PUBLISHER") "Altium Limited"))
      (libsource (lib "Miscellaneous Devices") (part "LED0"))
    )
    (comp (ref "D162")
      (value "~")
      (footprint "LED-UPRIGHT")
      (description "Typical INFRARED GaAs LED")
      (fields (field (name "MANUFACTURER") "Generic Components") (field (name "PUBLISHER") "Altium Limited"))
      (libsource (lib "Miscellaneous Devices") (part "LED0"))
    )
    (comp (ref "D163")
      (value "~")
      (footprint "LED-UPRIGHT")
      (description "Typical INFRARED GaAs LED")
      (fields (field (name "MANUFACTURER") "Generic Components") (field (name "PUBLISHER") "Altium Limited"))
      (libsource (lib "Miscellaneous Devices") (part "LED0"))
    )
    (comp (ref "D164")
      (value "~")
      (footprint "LED-UPRIGHT")
      (description "Typical INFRARED GaAs LED")
      (fields (field (name "MANUFACTURER") "Generic Components") (field (name "PUBLISHER") "Altium Limited"))
      (libsource (lib "Miscellaneous Devices") (part "LED0"))
    )
    (comp (ref "D165")
      (value "~")
      (footprint "LED-UPRIGHT")
      (description "Typical INFRARED GaAs LED")
      (fields (field (name "MANUFACTURER") "Generic Components") (field (name "PUBLISHER") "Altium Limited"))
      (libsource (lib "Miscellaneous Devices") (part "LED0"))
    )
    (comp (ref "D166")
      (value "~")
      (footprint "LED-UPRIGHT")
      (description "Typical INFRARED GaAs LED")
      (fields (field (name "MANUFACTURER") "Generic Components") (field (name "PUBLISHER") "Altium Limited"))
      (libsource (lib "Miscellaneous Devices") (part "LED0"))
    )
    (comp (ref "D167")
      (value "~")
      (footprint "LED-UPRIGHT")
      (description "Typical INFRARED GaAs LED")
      (fields (field (name "MANUFACTURER") "Generic Components") (field (name "PUBLISHER") "Altium Limited"))
      (libsource (lib "Miscellaneous Devices") (part "LED0"))
    )
    (comp (ref "D168")
      (value "~")
      (footprint "LED-UPRIGHT")
      (description "Typical INFRARED GaAs LED")
      (fields (field (name "MANUFACTURER") "Generic Components") (field (name "PUBLISHER") "Altium Limited"))
      (libsource (lib "Miscellaneous Devices") (part "LED0"))
    )
    (comp (ref "D169")
      (value "~")
      (footprint "LED-UPRIGHT")
      (description "Typical INFRARED GaAs LED")
      (fields (field (name "MANUFACTURER") "Generic Components") (field (name "PUBLISHER") "Altium Limited"))
      (libsource (lib "Miscellaneous Devices") (part "LED0"))
    )
    (comp (ref "D170")
      (value "~")
      (footprint "LED-UPRIGHT")
      (description "Typical INFRARED GaAs LED")
      (fields (field (name "MANUFACTURER") "Generic Components") (field (name "PUBLISHER") "Altium Limited"))
      (libsource (lib "Miscellaneous Devices") (part "LED0"))
    )
    (comp (ref "D171")
      (value "~")
      (footprint "LED-UPRIGHT")
      (description "Typical INFRARED GaAs LED")
      (fields (field (name "MANUFACTURER") "Generic Components") (field (name "PUBLISHER") "Altium Limited"))
      (libsource (lib "Miscellaneous Devices") (part "LED0"))
    )
    (comp (ref "D172")
      (value "~")
      (footprint "LED-UPRIGHT")
      (description "Typical INFRARED GaAs LED")
      (fields (field (name "MANUFACTURER") "Generic Components") (field (name "PUBLISHER") "Altium Limited"))
      (libsource (lib "Miscellaneous Devices") (part "LED0"))
    )
    (comp (ref "D173")
      (value "~")
      (footprint "LED-UPRIGHT")
      (description "Typical INFRARED GaAs LED")
      (fields (field (name "MANUFACTURER") "Generic Components") (field (name "PUBLISHER") "Altium Limited"))
      (libsource (lib "Miscellaneous Devices") (part "LED0"))
    )
    (comp (ref "D174")
      (value "~")
      (footprint "LED-UPRIGHT")
      (description "Typical INFRARED GaAs LED")
      (fields (field (name "MANUFACTURER") "Generic Components") (field (name "PUBLISHER") "Altium Limited"))
      (libsource (lib "Miscellaneous Devices") (part "LED0"))
    )
    (comp (ref "D175")
      (value "~")
      (footprint "LED-UPRIGHT")
      (description "Typical INFRARED GaAs LED")
      (fields (field (name "MANUFACTURER") "Generic Components") (field (name "PUBLISHER") "Altium Limited"))
      (libsource (lib "Miscellaneous Devices") (part "LED0"))
    )
    (comp (ref "D176")
      (value "~")
      (footprint "LED-UPRIGHT")
      (description "Typical INFRARED GaAs LED")
      (fields (field (name "MANUFACTURER") "Generic Components") (field (name "PUBLISHER") "Altium Limited"))
      (libsource (lib "Miscellaneous Devices") (part "LED0"))
    )
    (comp (ref "D177")
      (value "~")
      (footprint "LED-UPRIGHT")
      (description "Typical INFRARED GaAs LED")
      (fields (field (name "MANUFACTURER") "Generic Components") (field (name "PUBLISHER") "Altium Limited"))
      (libsource (lib "Miscellaneous Devices") (part "LED0"))
    )
    (comp (ref "D178")
      (value "~")
      (footprint "LED-UPRIGHT")
      (description "Typical INFRARED GaAs LED")
      (fields (field (name "MANUFACTURER") "Generic Components") (field (name "PUBLISHER") "Altium Limited"))
      (libsource (lib "Miscellaneous Devices") (part "LED0"))
    )
    (comp (ref "D179")
      (value "~")
      (footprint "LED-UPRIGHT")
      (description "Typical INFRARED GaAs LED")
      (fields (field (name "MANUFACTURER") "Generic Components") (field (name "PUBLISHER") "Altium Limited"))
      (libsource (lib "Miscellaneous Devices") (part "LED0"))
    )
    (comp (ref "D180")
      (value "~")
      (footprint "LED-UPRIGHT")
      (description "Typical INFRARED GaAs LED")
      (fields (field (name "MANUFACTURER") "Generic Components") (field (name "PUBLISHER") "Altium Limited"))
      (libsource (lib "Miscellaneous Devices") (part "LED0"))
    )
    (comp (ref "D181")
      (value "~")
      (footprint "LED-UPRIGHT")
      (description "Typical INFRARED GaAs LED")
      (fields (field (name "MANUFACTURER") "Generic Components") (field (name "PUBLISHER") "Altium Limited"))
      (libsource (lib "Miscellaneous Devices") (part "LED0"))
    )
    (comp (ref "D182")
      (value "~")
      (footprint "LED-UPRIGHT")
      (description "Typical INFRARED GaAs LED")
      (fields (field (name "MANUFACTURER") "Generic Components") (field (name "PUBLISHER") "Altium Limited"))
      (libsource (lib "Miscellaneous Devices") (part "LED0"))
    )
    (comp (ref "D183")
      (value "~")
      (footprint "LED-UPRIGHT")
      (description "Typical INFRARED GaAs LED")
      (fields (field (name "MANUFACTURER") "Generic Components") (field (name "PUBLISHER") "Altium Limited"))
      (libsource (lib "Miscellaneous Devices") (part "LED0"))
    )
    (comp (ref "D184")
      (value "~")
      (footprint "LED-UPRIGHT")
      (description "Typical INFRARED GaAs LED")
      (fields (field (name "MANUFACTURER") "Generic Components") (field (name "PUBLISHER") "Altium Limited"))
      (libsource (lib "Miscellaneous Devices") (part "LED0"))
    )
    (comp (ref "D185")
      (value "~")
      (footprint "LED-UPRIGHT")
      (description "Typical INFRARED GaAs LED")
      (fields (field (name "MANUFACTURER") "Generic Components") (field (name "PUBLISHER") "Altium Limited"))
      (libsource (lib "Miscellaneous Devices") (part "LED0"))
    )
    (comp (ref "D186")
      (value "~")
      (footprint "LED-UPRIGHT")
      (description "Typical INFRARED GaAs LED")
      (fields (field (name "MANUFACTURER") "Generic Components") (field (name "PUBLISHER") "Altium Limited"))
      (libsource (lib "Miscellaneous Devices") (part "LED0"))
    )
    (comp (ref "D187")
      (value "~")
      (footprint "LED-UPRIGHT")
      (description "Typical INFRARED GaAs LED")
      (fields (field (name "MANUFACTURER") "Generic Components") (field (name "PUBLISHER") "Altium Limited"))
      (libsource (lib "Miscellaneous Devices") (part "LED0"))
    )
    (comp (ref "D188")
      (value "~")
      (footprint "LED-UPRIGHT")
      (description "Typical INFRARED GaAs LED")
      (fields (field (name "MANUFACTURER") "Generic Components") (field (name "PUBLISHER") "Altium Limited"))
      (libsource (lib "Miscellaneous Devices") (part "LED0"))
    )
    (comp (ref "D189")
      (value "~")
      (footprint "LED-UPRIGHT")
      (description "Typical INFRARED GaAs LED")
      (fields (field (name "MANUFACTURER") "Generic Components") (field (name "PUBLISHER") "Altium Limited"))
      (libsource (lib "Miscellaneous Devices") (part "LED0"))
    )
    (comp (ref "D190")
      (value "~")
      (footprint "LED-UPRIGHT")
      (description "Typical INFRARED GaAs LED")
      (fields (field (name "MANUFACTURER") "Generic Components") (field (name "PUBLISHER") "Altium Limited"))
      (libsource (lib "Miscellaneous Devices") (part "LED0"))
    )
    (comp (ref "D191")
      (value "~")
      (footprint "LED-UPRIGHT")
      (description "Typical INFRARED GaAs LED")
      (fields (field (name "MANUFACTURER") "Generic Components") (field (name "PUBLISHER") "Altium Limited"))
      (libsource (lib "Miscellaneous Devices") (part "LED0"))
    )
    (comp (ref "D192")
      (value "~")
      (footprint "LED-UPRIGHT")
      (description "Typical INFRARED GaAs LED")
      (fields (field (name "MANUFACTURER") "Generic Components") (field (name "PUBLISHER") "Altium Limited"))
      (libsource (lib "Miscellaneous Devices") (part "LED0"))
    )
    (comp (ref "D193")
      (value "~")
      (footprint "LED-UPRIGHT")
      (description "Typical INFRARED GaAs LED")
      (fields (field (name "MANUFACTURER") "Generic Components") (field (name "PUBLISHER") "Altium Limited"))
      (libsource (lib "Miscellaneous Devices") (part "LED0"))
    )
    (comp (ref "D194")
      (value "~")
      (footprint "LED-UPRIGHT")
      (description "Typical INFRARED GaAs LED")
      (fields (field (name "MANUFACTURER") "Generic Components") (field (name "PUBLISHER") "Altium Limited"))
      (libsource (lib "Miscellaneous Devices") (part "LED0"))
    )
    (comp (ref "D195")
      (value "~")
      (footprint "LED-UPRIGHT")
      (description "Typical INFRARED GaAs LED")
      (fields (field (name "MANUFACTURER") "Generic Components") (field (name "PUBLISHER") "Altium Limited"))
      (libsource (lib "Miscellaneous Devices") (part "LED0"))
    )
    (comp (ref "D196")
      (value "~")
      (footprint "LED-UPRIGHT")
      (description "Typical INFRARED GaAs LED")
      (fields (field (name "MANUFACTURER") "Generic Components") (field (name "PUBLISHER") "Altium Limited"))
      (libsource (lib "Miscellaneous Devices") (part "LED0"))
    )
    (comp (ref "D197")
      (value "~")
      (footprint "LED-UPRIGHT")
      (description "Typical INFRARED GaAs LED")
      (fields (field (name "MANUFACTURER") "Generic Components") (field (name "PUBLISHER") "Altium Limited"))
      (libsource (lib "Miscellaneous Devices") (part "LED0"))
    )
    (comp (ref "D198")
      (value "~")
      (footprint "LED-UPRIGHT")
      (description "Typical INFRARED GaAs LED")
      (fields (field (name "MANUFACTURER") "Generic Components") (field (name "PUBLISHER") "Altium Limited"))
      (libsource (lib "Miscellaneous Devices") (part "LED0"))
    )
    (comp (ref "D199")
      (value "~")
      (footprint "LED-UPRIGHT")
      (description "Typical INFRARED GaAs LED")
      (fields (field (name "MANUFACTURER") "Generic Components") (field (name "PUBLISHER") "Altium Limited"))
      (libsource (lib "Miscellaneous Devices") (part "LED0"))
    )
    (comp (ref "D200")
      (value "~")
      (footprint "LED-UPRIGHT")
      (description "Typical INFRARED GaAs LED")
      (fields (field (name "MANUFACTURER") "Generic Components") (field (name "PUBLISHER") "Altium Limited"))
      (libsource (lib "Miscellaneous Devices") (part "LED0"))
    )
    (comp (ref "D201")
      (value "~")
      (footprint "LED-UPRIGHT")
      (description "Typical INFRARED GaAs LED")
      (fields (field (name "MANUFACTURER") "Generic Components") (field (name "PUBLISHER") "Altium Limited"))
      (libsource (lib "Miscellaneous Devices") (part "LED0"))
    )
    (comp (ref "D202")
      (value "~")
      (footprint "LED-UPRIGHT")
      (description "Typical INFRARED GaAs LED")
      (fields (field (name "MANUFACTURER") "Generic Components") (field (name "PUBLISHER") "Altium Limited"))
      (libsource (lib "Miscellaneous Devices") (part "LED0"))
    )
    (comp (ref "D203")
      (value "~")
      (footprint "LED-UPRIGHT")
      (description "Typical INFRARED GaAs LED")
      (fields (field (name "MANUFACTURER") "Generic Components") (field (name "PUBLISHER") "Altium Limited"))
      (libsource (lib "Miscellaneous Devices") (part "LED0"))
    )
    (comp (ref "D204")
      (value "~")
      (footprint "LED-UPRIGHT")
      (description "Typical INFRARED GaAs LED")
      (fields (field (name "MANUFACTURER") "Generic Components") (field (name "PUBLISHER") "Altium Limited"))
      (libsource (lib "Miscellaneous Devices") (part "LED0"))
    )
    (comp (ref "D205")
      (value "~")
      (footprint "LED-UPRIGHT")
      (description "Typical INFRARED GaAs LED")
      (fields (field (name "MANUFACTURER") "Generic Components") (field (name "PUBLISHER") "Altium Limited"))
      (libsource (lib "Miscellaneous Devices") (part "LED0"))
    )
    (comp (ref "D206")
      (value "~")
      (footprint "LED-UPRIGHT")
      (description "Typical INFRARED GaAs LED")
      (fields (field (name "MANUFACTURER") "Generic Components") (field (name "PUBLISHER") "Altium Limited"))
      (libsource (lib "Miscellaneous Devices") (part "LED0"))
    )
    (comp (ref "D207")
      (value "~")
      (footprint "LED-UPRIGHT")
      (description "Typical INFRARED GaAs LED")
      (fields (field (name "MANUFACTURER") "Generic Components") (field (name "PUBLISHER") "Altium Limited"))
      (libsource (lib "Miscellaneous Devices") (part "LED0"))
    )
    (comp (ref "D208")
      (value "~")
      (footprint "LED-UPRIGHT")
      (description "Typical INFRARED GaAs LED")
      (fields (field (name "MANUFACTURER") "Generic Components") (field (name "PUBLISHER") "Altium Limited"))
      (libsource (lib "Miscellaneous Devices") (part "LED0"))
    )
    (comp (ref "D209")
      (value "~")
      (footprint "LED-UPRIGHT")
      (description "Typical INFRARED GaAs LED")
      (fields (field (name "MANUFACTURER") "Generic Components") (field (name "PUBLISHER") "Altium Limited"))
      (libsource (lib "Miscellaneous Devices") (part "LED0"))
    )
    (comp (ref "D210")
      (value "~")
      (footprint "LED-UPRIGHT")
      (description "Typical INFRARED GaAs LED")
      (fields (field (name "MANUFACTURER") "Generic Components") (field (name "PUBLISHER") "Altium Limited"))
      (libsource (lib "Miscellaneous Devices") (part "LED0"))
    )
    (comp (ref "D211")
      (value "~")
      (footprint "LED-UPRIGHT")
      (description "Typical INFRARED GaAs LED")
      (fields (field (name "MANUFACTURER") "Generic Components") (field (name "PUBLISHER") "Altium Limited"))
      (libsource (lib "Miscellaneous Devices") (part "LED0"))
    )
    (comp (ref "D212")
      (value "~")
      (footprint "LED-UPRIGHT")
      (description "Typical INFRARED GaAs LED")
      (fields (field (name "MANUFACTURER") "Generic Components") (field (name "PUBLISHER") "Altium Limited"))
      (libsource (lib "Miscellaneous Devices") (part "LED0"))
    )
    (comp (ref "D213")
      (value "~")
      (footprint "LED-UPRIGHT")
      (description "Typical INFRARED GaAs LED")
      (fields (field (name "MANUFACTURER") "Generic Components") (field (name "PUBLISHER") "Altium Limited"))
      (libsource (lib "Miscellaneous Devices") (part "LED0"))
    )
    (comp (ref "D214")
      (value "~")
      (footprint "LED-UPRIGHT")
      (description "Typical INFRARED GaAs LED")
      (fields (field (name "MANUFACTURER") "Generic Components") (field (name "PUBLISHER") "Altium Limited"))
      (libsource (lib "Miscellaneous Devices") (part "LED0"))
    )
    (comp (ref "D215")
      (value "~")
      (footprint "LED-UPRIGHT")
      (description "Typical INFRARED GaAs LED")
      (fields (field (name "MANUFACTURER") "Generic Components") (field (name "PUBLISHER") "Altium Limited"))
      (libsource (lib "Miscellaneous Devices") (part "LED0"))
    )
    (comp (ref "D216")
      (value "~")
      (footprint "LED-UPRIGHT")
      (description "Typical INFRARED GaAs LED")
      (fields (field (name "MANUFACTURER") "Generic Components") (field (name "PUBLISHER") "Altium Limited"))
      (libsource (lib "Miscellaneous Devices") (part "LED0"))
    )
    (comp (ref "D217")
      (value "~")
      (footprint "LED-UPRIGHT")
      (description "Typical INFRARED GaAs LED")
      (fields (field (name "MANUFACTURER") "Generic Components") (field (name "PUBLISHER") "Altium Limited"))
      (libsource (lib "Miscellaneous Devices") (part "LED0"))
    )
    (comp (ref "D218")
      (value "~")
      (footprint "LED-UPRIGHT")
      (description "Typical INFRARED GaAs LED")
      (fields (field (name "MANUFACTURER") "Generic Components") (field (name "PUBLISHER") "Altium Limited"))
      (libsource (lib "Miscellaneous Devices") (part "LED0"))
    )
    (comp (ref "D219")
      (value "~")
      (footprint "LED-UPRIGHT")
      (description "Typical INFRARED GaAs LED")
      (fields (field (name "MANUFACTURER") "Generic Components") (field (name "PUBLISHER") "Altium Limited"))
      (libsource (lib "Miscellaneous Devices") (part "LED0"))
    )
    (comp (ref "D220")
      (value "~")
      (footprint "LED-UPRIGHT")
      (description "Typical INFRARED GaAs LED")
      (fields (field (name "MANUFACTURER") "Generic Components") (field (name "PUBLISHER") "Altium Limited"))
      (libsource (lib "Miscellaneous Devices") (part "LED0"))
    )
    (comp (ref "D221")
      (value "~")
      (footprint "LED-UPRIGHT")
      (description "Typical INFRARED GaAs LED")
      (fields (field (name "MANUFACTURER") "Generic Components") (field (name "PUBLISHER") "Altium Limited"))
      (libsource (lib "Miscellaneous Devices") (part "LED0"))
    )
    (comp (ref "D222")
      (value "~")
      (footprint "LED-UPRIGHT")
      (description "Typical INFRARED GaAs LED")
      (fields (field (name "MANUFACTURER") "Generic Components") (field (name "PUBLISHER") "Altium Limited"))
      (libsource (lib "Miscellaneous Devices") (part "LED0"))
    )
    (comp (ref "D223")
      (value "~")
      (footprint "LED-UPRIGHT")
      (description "Typical INFRARED GaAs LED")
      (fields (field (name "MANUFACTURER") "Generic Components") (field (name "PUBLISHER") "Altium Limited"))
      (libsource (lib "Miscellaneous Devices") (part "LED0"))
    )
    (comp (ref "D224")
      (value "~")
      (footprint "LED-UPRIGHT")
      (description "Typical INFRARED GaAs LED")
      (fields (field (name "MANUFACTURER") "Generic Components") (field (name "PUBLISHER") "Altium Limited"))
      (libsource (lib "Miscellaneous Devices") (part "LED0"))
    )
    (comp (ref "D225")
      (value "~")
      (footprint "LED-UPRIGHT")
      (description "Typical INFRARED GaAs LED")
      (fields (field (name "MANUFACTURER") "Generic Components") (field (name "PUBLISHER") "Altium Limited"))
      (libsource (lib "Miscellaneous Devices") (part "LED0"))
    )
    (comp (ref "D226")
      (value "~")
      (footprint "LED-UPRIGHT")
      (description "Typical INFRARED GaAs LED")
      (fields (field (name "MANUFACTURER") "Generic Components") (field (name "PUBLISHER") "Altium Limited"))
      (libsource (lib "Miscellaneous Devices") (part "LED0"))
    )
    (comp (ref "D227")
      (value "~")
      (footprint "LED-UPRIGHT")
      (description "Typical INFRARED GaAs LED")
      (fields (field (name "MANUFACTURER") "Generic Components") (field (name "PUBLISHER") "Altium Limited"))
      (libsource (lib "Miscellaneous Devices") (part "LED0"))
    )
    (comp (ref "D228")
      (value "~")
      (footprint "LED-UPRIGHT")
      (description "Typical INFRARED GaAs LED")
      (fields (field (name "MANUFACTURER") "Generic Components") (field (name "PUBLISHER") "Altium Limited"))
      (libsource (lib "Miscellaneous Devices") (part "LED0"))
    )
    (comp (ref "D229")
      (value "~")
      (footprint "LED-UPRIGHT")
      (description "Typical INFRARED GaAs LED")
      (fields (field (name "MANUFACTURER") "Generic Components") (field (name "PUBLISHER") "Altium Limited"))
      (libsource (lib "Miscellaneous Devices") (part "LED0"))
    )
    (comp (ref "D230")
      (value "~")
      (footprint "LED-UPRIGHT")
      (description "Typical INFRARED GaAs LED")
      (fields (field (name "MANUFACTURER") "Generic Components") (field (name "PUBLISHER") "Altium Limited"))
      (libsource (lib "Miscellaneous Devices") (part "LED0"))
    )
    (comp (ref "D231")
      (value "~")
      (footprint "LED-UPRIGHT")
      (description "Typical INFRARED GaAs LED")
      (fields (field (name "MANUFACTURER") "Generic Components") (field (name "PUBLISHER") "Altium Limited"))
      (libsource (lib "Miscellaneous Devices") (part "LED0"))
    )
    (comp (ref "D232")
      (value "~")
      (footprint "LED-UPRIGHT")
      (description "Typical INFRARED GaAs LED")
      (fields (field (name "MANUFACTURER") "Generic Components") (field (name "PUBLISHER") "Altium Limited"))
      (libsource (lib "Miscellaneous Devices") (part "LED0"))
    )
    (comp (ref "D233")
      (value "~")
      (footprint "LED-UPRIGHT")
      (description "Typical INFRARED GaAs LED")
      (fields (field (name "MANUFACTURER") "Generic Components") (field (name "PUBLISHER") "Altium Limited"))
      (libsource (lib "Miscellaneous Devices") (part "LED0"))
    )
    (comp (ref "D234")
      (value "~")
      (footprint "LED-UPRIGHT")
      (description "Typical INFRARED GaAs LED")
      (fields (field (name "MANUFACTURER") "Generic Components") (field (name "PUBLISHER") "Altium Limited"))
      (libsource (lib "Miscellaneous Devices") (part "LED0"))
    )
    (comp (ref "D235")
      (value "~")
      (footprint "LED-UPRIGHT")
      (description "Typical INFRARED GaAs LED")
      (fields (field (name "MANUFACTURER") "Generic Components") (field (name "PUBLISHER") "Altium Limited"))
      (libsource (lib "Miscellaneous Devices") (part "LED0"))
    )
    (comp (ref "D236")
      (value "~")
      (footprint "LED-UPRIGHT")
      (description "Typical INFRARED GaAs LED")
      (fields (field (name "MANUFACTURER") "Generic Components") (field (name "PUBLISHER") "Altium Limited"))
      (libsource (lib "Miscellaneous Devices") (part "LED0"))
    )
    (comp (ref "D237")
      (value "~")
      (footprint "LED-UPRIGHT")
      (description "Typical INFRARED GaAs LED")
      (fields (field (name "MANUFACTURER") "Generic Components") (field (name "PUBLISHER") "Altium Limited"))
      (libsource (lib "Miscellaneous Devices") (part "LED0"))
    )
    (comp (ref "D238")
      (value "~")
      (footprint "LED-UPRIGHT")
      (description "Typical INFRARED GaAs LED")
      (fields (field (name "MANUFACTURER") "Generic Components") (field (name "PUBLISHER") "Altium Limited"))
      (libsource (lib "Miscellaneous Devices") (part "LED0"))
    )
    (comp (ref "D239")
      (value "~")
      (footprint "LED-UPRIGHT")
      (description "Typical INFRARED GaAs LED")
      (fields (field (name "MANUFACTURER") "Generic Components") (field (name "PUBLISHER") "Altium Limited"))
      (libsource (lib "Miscellaneous Devices") (part "LED0"))
    )
    (comp (ref "D240")
      (value "~")
      (footprint "LED-UPRIGHT")
      (description "Typical INFRARED GaAs LED")
      (fields (field (name "MANUFACTURER") "Generic Components") (field (name "PUBLISHER") "Altium Limited"))
      (libsource (lib "Miscellaneous Devices") (part "LED0"))
    )
    (comp (ref "D241")
      (value "~")
      (footprint "LED-UPRIGHT")
      (description "Typical INFRARED GaAs LED")
      (fields (field (name "MANUFACTURER") "Generic Components") (field (name "PUBLISHER") "Altium Limited"))
      (libsource (lib "Miscellaneous Devices") (part "LED0"))
    )
    (comp (ref "D242")
      (value "~")
      (footprint "LED-UPRIGHT")
      (description "Typical INFRARED GaAs LED")
      (fields (field (name "MANUFACTURER") "Generic Components") (field (name "PUBLISHER") "Altium Limited"))
      (libsource (lib "Miscellaneous Devices") (part "LED0"))
    )
    (comp (ref "D243")
      (value "~")
      (footprint "LED-UPRIGHT")
      (description "Typical INFRARED GaAs LED")
      (fields (field (name "MANUFACTURER") "Generic Components") (field (name "PUBLISHER") "Altium Limited"))
      (libsource (lib "Miscellaneous Devices") (part "LED0"))
    )
    (comp (ref "D244")
      (value "~")
      (footprint "LED-UPRIGHT")
      (description "Typical INFRARED GaAs LED")
      (fields (field (name "MANUFACTURER") "Generic Components") (field (name "PUBLISHER") "Altium Limited"))
      (libsource (lib "Miscellaneous Devices") (part "LED0"))
    )
    (comp (ref "D245")
      (value "~")
      (footprint "LED-UPRIGHT")
      (description "Typical INFRARED GaAs LED")
      (fields (field (name "MANUFACTURER") "Generic Components") (field (name "PUBLISHER") "Altium Limited"))
      (libsource (lib "Miscellaneous Devices") (part "LED0"))
    )
    (comp (ref "D246")
      (value "~")
      (footprint "LED-UPRIGHT")
      (description "Typical INFRARED GaAs LED")
      (fields (field (name "MANUFACTURER") "Generic Components") (field (name "PUBLISHER") "Altium Limited"))
      (libsource (lib "Miscellaneous Devices") (part "LED0"))
    )
    (comp (ref "D247")
      (value "~")
      (footprint "LED-UPRIGHT")
      (description "Typical INFRARED GaAs LED")
      (fields (field (name "MANUFACTURER") "Generic Components") (field (name "PUBLISHER") "Altium Limited"))
      (libsource (lib "Miscellaneous Devices") (part "LED0"))
    )
    (comp (ref "D248")
      (value "~")
      (footprint "LED-UPRIGHT")
      (description "Typical INFRARED GaAs LED")
      (fields (field (name "MANUFACTURER") "Generic Components") (field (name "PUBLISHER") "Altium Limited"))
      (libsource (lib "Miscellaneous Devices") (part "LED0"))
    )
    (comp (ref "D249")
      (value "~")
      (footprint "LED-UPRIGHT")
      (description "Typical INFRARED GaAs LED")
      (fields (field (name "MANUFACTURER") "Generic Components") (field (name "PUBLISHER") "Altium Limited"))
      (libsource (lib "Miscellaneous Devices") (part "LED0"))
    )
    (comp (ref "D250")
      (value "~")
      (footprint "LED-UPRIGHT")
      (description "Typical INFRARED GaAs LED")
      (fields (field (name "MANUFACTURER") "Generic Components") (field (name "PUBLISHER") "Altium Limited"))
      (libsource (lib "Miscellaneous Devices") (part "LED0"))
    )
    (comp (ref "D251")
      (value "~")
      (footprint "LED-UPRIGHT")
      (description "Typical INFRARED GaAs LED")
      (fields (field (name "MANUFACTURER") "Generic Components") (field (name "PUBLISHER") "Altium Limited"))
      (libsource (lib "Miscellaneous Devices") (part "LED0"))
    )
    (comp (ref "D252")
      (value "~")
      (footprint "LED-UPRIGHT")
      (description "Typical INFRARED GaAs LED")
      (fields (field (name "MANUFACTURER") "Generic Components") (field (name "PUBLISHER") "Altium Limited"))
      (libsource (lib "Miscellaneous Devices") (part "LED0"))
    )
    (comp (ref "D253")
      (value "~")
      (footprint "LED-UPRIGHT")
      (description "Typical INFRARED GaAs LED")
      (fields (field (name "MANUFACTURER") "Generic Components") (field (name "PUBLISHER") "Altium Limited"))
      (libsource (lib "Miscellaneous Devices") (part "LED0"))
    )
    (comp (ref "D254")
      (value "~")
      (footprint "LED-UPRIGHT")
      (description "Typical INFRARED GaAs LED")
      (fields (field (name "MANUFACTURER") "Generic Components") (field (name "PUBLISHER") "Altium Limited"))
      (libsource (lib "Miscellaneous Devices") (part "LED0"))
    )
    (comp (ref "D255")
      (value "~")
      (footprint "LED-UPRIGHT")
      (description "Typical INFRARED GaAs LED")
      (fields (field (name "MANUFACTURER") "Generic Components") (field (name "PUBLISHER") "Altium Limited"))
      (libsource (lib "Miscellaneous Devices") (part "LED0"))
    )
    (comp (ref "D256")
      (value "~")
      (footprint "LED-UPRIGHT")
      (description "Typical INFRARED GaAs LED")
      (fields (field (name "MANUFACTURER") "Generic Components") (field (name "PUBLISHER") "Altium Limited"))
      (libsource (lib "Miscellaneous Devices") (part "LED0"))
    )
    (comp (ref "D257")
      (value "~")
      (footprint "LED-UPRIGHT")
      (description "Typical INFRARED GaAs LED")
      (fields (field (name "MANUFACTURER") "Generic Components") (field (name "PUBLISHER") "Altium Limited"))
      (libsource (lib "Miscellaneous Devices") (part "LED0"))
    )
    (comp (ref "D258")
      (value "~")
      (footprint "LED-UPRIGHT")
      (description "Typical INFRARED GaAs LED")
      (fields (field (name "MANUFACTURER") "Generic Components") (field (name "PUBLISHER") "Altium Limited"))
      (libsource (lib "Miscellaneous Devices") (part "LED0"))
    )
    (comp (ref "D259")
      (value "~")
      (footprint "LED-UPRIGHT")
      (description "Typical INFRARED GaAs LED")
      (fields (field (name "MANUFACTURER") "Generic Components") (field (name "PUBLISHER") "Altium Limited"))
      (libsource (lib "Miscellaneous Devices") (part "LED0"))
    )
    (comp (ref "D260")
      (value "~")
      (footprint "LED-UPRIGHT")
      (description "Typical INFRARED GaAs LED")
      (fields (field (name "MANUFACTURER") "Generic Components") (field (name "PUBLISHER") "Altium Limited"))
      (libsource (lib "Miscellaneous Devices") (part "LED0"))
    )
    (comp (ref "D261")
      (value "~")
      (footprint "LED-UPRIGHT")
      (description "Typical INFRARED GaAs LED")
      (fields (field (name "MANUFACTURER") "Generic Components") (field (name "PUBLISHER") "Altium Limited"))
      (libsource (lib "Miscellaneous Devices") (part "LED0"))
    )
    (comp (ref "D262")
      (value "~")
      (footprint "LED-UPRIGHT")
      (description "Typical INFRARED GaAs LED")
      (fields (field (name "MANUFACTURER") "Generic Components") (field (name "PUBLISHER") "Altium Limited"))
      (libsource (lib "Miscellaneous Devices") (part "LED0"))
    )
    (comp (ref "D263")
      (value "~")
      (footprint "LED-UPRIGHT")
      (description "Typical INFRARED GaAs LED")
      (fields (field (name "MANUFACTURER") "Generic Components") (field (name "PUBLISHER") "Altium Limited"))
      (libsource (lib "Miscellaneous Devices") (part "LED0"))
    )
    (comp (ref "D264")
      (value "~")
      (footprint "LED-UPRIGHT")
      (description "Typical INFRARED GaAs LED")
      (fields (field (name "MANUFACTURER") "Generic Components") (field (name "PUBLISHER") "Altium Limited"))
      (libsource (lib "Miscellaneous Devices") (part "LED0"))
    )
    (comp (ref "D265")
      (value "~")
      (footprint "LED-UPRIGHT")
      (description "Typical INFRARED GaAs LED")
      (fields (field (name "MANUFACTURER") "Generic Components") (field (name "PUBLISHER") "Altium Limited"))
      (libsource (lib "Miscellaneous Devices") (part "LED0"))
    )
    (comp (ref "D266")
      (value "~")
      (footprint "LED-UPRIGHT")
      (description "Typical INFRARED GaAs LED")
      (fields (field (name "MANUFACTURER") "Generic Components") (field (name "PUBLISHER") "Altium Limited"))
      (libsource (lib "Miscellaneous Devices") (part "LED0"))
    )
    (comp (ref "D267")
      (value "~")
      (footprint "LED-UPRIGHT")
      (description "Typical INFRARED GaAs LED")
      (fields (field (name "MANUFACTURER") "Generic Components") (field (name "PUBLISHER") "Altium Limited"))
      (libsource (lib "Miscellaneous Devices") (part "LED0"))
    )
    (comp (ref "D268")
      (value "~")
      (footprint "LED-UPRIGHT")
      (description "Typical INFRARED GaAs LED")
      (fields (field (name "MANUFACTURER") "Generic Components") (field (name "PUBLISHER") "Altium Limited"))
      (libsource (lib "Miscellaneous Devices") (part "LED0"))
    )
    (comp (ref "D269")
      (value "~")
      (footprint "LED-UPRIGHT")
      (description "Typical INFRARED GaAs LED")
      (fields (field (name "MANUFACTURER") "Generic Components") (field (name "PUBLISHER") "Altium Limited"))
      (libsource (lib "Miscellaneous Devices") (part "LED0"))
    )
    (comp (ref "D270")
      (value "~")
      (footprint "LED-UPRIGHT")
      (description "Typical INFRARED GaAs LED")
      (fields (field (name "MANUFACTURER") "Generic Components") (field (name "PUBLISHER") "Altium Limited"))
      (libsource (lib "Miscellaneous Devices") (part "LED0"))
    )
    (comp (ref "D271")
      (value "~")
      (footprint "LED-UPRIGHT")
      (description "Typical INFRARED GaAs LED")
      (fields (field (name "MANUFACTURER") "Generic Components") (field (name "PUBLISHER") "Altium Limited"))
      (libsource (lib "Miscellaneous Devices") (part "LED0"))
    )
    (comp (ref "D272")
      (value "~")
      (footprint "LED-UPRIGHT")
      (description "Typical INFRARED GaAs LED")
      (fields (field (name "MANUFACTURER") "Generic Components") (field (name "PUBLISHER") "Altium Limited"))
      (libsource (lib "Miscellaneous Devices") (part "LED0"))
    )
    (comp (ref "D273")
      (value "~")
      (footprint "LED-UPRIGHT")
      (description "Typical INFRARED GaAs LED")
      (fields (field (name "MANUFACTURER") "Generic Components") (field (name "PUBLISHER") "Altium Limited"))
      (libsource (lib "Miscellaneous Devices") (part "LED0"))
    )
    (comp (ref "D274")
      (value "~")
      (footprint "LED-UPRIGHT")
      (description "Typical INFRARED GaAs LED")
      (fields (field (name "MANUFACTURER") "Generic Components") (field (name "PUBLISHER") "Altium Limited"))
      (libsource (lib "Miscellaneous Devices") (part "LED0"))
    )
    (comp (ref "D275")
      (value "~")
      (footprint "LED-UPRIGHT")
      (description "Typical INFRARED GaAs LED")
      (fields (field (name "MANUFACTURER") "Generic Components") (field (name "PUBLISHER") "Altium Limited"))
      (libsource (lib "Miscellaneous Devices") (part "LED0"))
    )
    (comp (ref "D276")
      (value "~")
      (footprint "LED-UPRIGHT")
      (description "Typical INFRARED GaAs LED")
      (fields (field (name "MANUFACTURER") "Generic Components") (field (name "PUBLISHER") "Altium Limited"))
      (libsource (lib "Miscellaneous Devices") (part "LED0"))
    )
    (comp (ref "D277")
      (value "~")
      (footprint "LED-UPRIGHT")
      (description "Typical INFRARED GaAs LED")
      (fields (field (name "MANUFACTURER") "Generic Components") (field (name "PUBLISHER") "Altium Limited"))
      (libsource (lib "Miscellaneous Devices") (part "LED0"))
    )
    (comp (ref "D278")
      (value "~")
      (footprint "LED-UPRIGHT")
      (description "Typical INFRARED GaAs LED")
      (fields (field (name "MANUFACTURER") "Generic Components") (field (name "PUBLISHER") "Altium Limited"))
      (libsource (lib "Miscellaneous Devices") (part "LED0"))
    )
    (comp (ref "D279")
      (value "~")
      (footprint "LED-UPRIGHT")
      (description "Typical INFRARED GaAs LED")
      (fields (field (name "MANUFACTURER") "Generic Components") (field (name "PUBLISHER") "Altium Limited"))
      (libsource (lib "Miscellaneous Devices") (part "LED0"))
    )
    (comp (ref "D280")
      (value "~")
      (footprint "LED-UPRIGHT")
      (description "Typical INFRARED GaAs LED")
      (fields (field (name "MANUFACTURER") "Generic Components") (field (name "PUBLISHER") "Altium Limited"))
      (libsource (lib "Miscellaneous Devices") (part "LED0"))
    )
    (comp (ref "D281")
      (value "~")
      (footprint "LED-UPRIGHT")
      (description "Typical INFRARED GaAs LED")
      (fields (field (name "MANUFACTURER") "Generic Components") (field (name "PUBLISHER") "Altium Limited"))
      (libsource (lib "Miscellaneous Devices") (part "LED0"))
    )
    (comp (ref "D282")
      (value "~")
      (footprint "LED-UPRIGHT")
      (description "Typical INFRARED GaAs LED")
      (fields (field (name "MANUFACTURER") "Generic Components") (field (name "PUBLISHER") "Altium Limited"))
      (libsource (lib "Miscellaneous Devices") (part "LED0"))
    )
    (comp (ref "D283")
      (value "~")
      (footprint "LED-UPRIGHT")
      (description "Typical INFRARED GaAs LED")
      (fields (field (name "MANUFACTURER") "Generic Components") (field (name "PUBLISHER") "Altium Limited"))
      (libsource (lib "Miscellaneous Devices") (part "LED0"))
    )
    (comp (ref "D284")
      (value "~")
      (footprint "LED-UPRIGHT")
      (description "Typical INFRARED GaAs LED")
      (fields (field (name "MANUFACTURER") "Generic Components") (field (name "PUBLISHER") "Altium Limited"))
      (libsource (lib "Miscellaneous Devices") (part "LED0"))
    )
    (comp (ref "D285")
      (value "~")
      (footprint "LED-UPRIGHT")
      (description "Typical INFRARED GaAs LED")
      (fields (field (name "MANUFACTURER") "Generic Components") (field (name "PUBLISHER") "Altium Limited"))
      (libsource (lib "Miscellaneous Devices") (part "LED0"))
    )
    (comp (ref "D286")
      (value "~")
      (footprint "LED-UPRIGHT")
      (description "Typical INFRARED GaAs LED")
      (fields (field (name "MANUFACTURER") "Generic Components") (field (name "PUBLISHER") "Altium Limited"))
      (libsource (lib "Miscellaneous Devices") (part "LED0"))
    )
    (comp (ref "D287")
      (value "~")
      (footprint "LED-UPRIGHT")
      (description "Typical INFRARED GaAs LED")
      (fields (field (name "MANUFACTURER") "Generic Components") (field (name "PUBLISHER") "Altium Limited"))
      (libsource (lib "Miscellaneous Devices") (part "LED0"))
    )
    (comp (ref "D288")
      (value "~")
      (footprint "LED-UPRIGHT")
      (description "Typical INFRARED GaAs LED")
      (fields (field (name "MANUFACTURER") "Generic Components") (field (name "PUBLISHER") "Altium Limited"))
      (libsource (lib "Miscellaneous Devices") (part "LED0"))
    )
  )
  (nets
    (net (code "1") (name "/COL<0>") (class "Default")
      (node (ref "D1") (pin "1") (pinfunction "A_1") (pintype "passive"))
      (node (ref "D113") (pin "1") (pinfunction "A_1") (pintype "passive"))
      (node (ref "D129") (pin "1") (pinfunction "A_1") (pintype "passive"))
      (node (ref "D145") (pin "1") (pinfunction "A_1") (pintype "passive"))
      (node (ref "D161") (pin "1") (pinfunction "A_1") (pintype "passive"))
      (node (ref "D17") (pin "1") (pinfunction "A_1") (pintype "passive"))
      (node (ref "D177") (pin "1") (pinfunction "A_1") (pintype "passive"))
      (node (ref "D193") (pin "1") (pinfunction "A_1") (pintype "passive"))
      (node (ref "D209") (pin "1") (pinfunction "A_1") (pintype "passive"))
      (node (ref "D225") (pin "1") (pinfunction "A_1") (pintype "passive"))
      (node (ref "D241") (pin "1") (pinfunction "A_1") (pintype "passive"))
      (node (ref "D257") (pin "1") (pinfunction "A_1") (pintype "passive"))
      (node (ref "D273") (pin "1") (pinfunction "A_1") (pintype "passive"))
      (node (ref "D33") (pin "1") (pinfunction "A_1") (pintype "passive"))
      (node (ref "D49") (pin "1") (pinfunction "A_1") (pintype "passive"))
      (node (ref "D65") (pin "1") (pinfunction "A_1") (pintype "passive"))
      (node (ref "D81") (pin "1") (pinfunction "A_1") (pintype "passive"))
      (node (ref "D97") (pin "1") (pinfunction "A_1") (pintype "passive"))
    )
    (net (code "2") (name "/COL<1>") (class "Default")
      (node (ref "D114") (pin "1") (pinfunction "A_1") (pintype "passive"))
      (node (ref "D130") (pin "1") (pinfunction "A_1") (pintype "passive"))
      (node (ref "D146") (pin "1") (pinfunction "A_1") (pintype "passive"))
      (node (ref "D162") (pin "1") (pinfunction "A_1") (pintype "passive"))
      (node (ref "D178") (pin "1") (pinfunction "A_1") (pintype "passive"))
      (node (ref "D18") (pin "1") (pinfunction "A_1") (pintype "passive"))
      (node (ref "D194") (pin "1") (pinfunction "A_1") (pintype "passive"))
      (node (ref "D2") (pin "1") (pinfunction "A_1") (pintype "passive"))
      (node (ref "D210") (pin "1") (pinfunction "A_1") (pintype "passive"))
      (node (ref "D226") (pin "1") (pinfunction "A_1") (pintype "passive"))
      (node (ref "D242") (pin "1") (pinfunction "A_1") (pintype "passive"))
      (node (ref "D258") (pin "1") (pinfunction "A_1") (pintype "passive"))
      (node (ref "D274") (pin "1") (pinfunction "A_1") (pintype "passive"))
      (node (ref "D34") (pin "1") (pinfunction "A_1") (pintype "passive"))
      (node (ref "D50") (pin "1") (pinfunction "A_1") (pintype "passive"))
      (node (ref "D66") (pin "1") (pinfunction "A_1") (pintype "passive"))
      (node (ref "D82") (pin "1") (pinfunction "A_1") (pintype "passive"))
      (node (ref "D98") (pin "1") (pinfunction "A_1") (pintype "passive"))
    )
    (net (code "3") (name "/COL<2>") (class "Default")
      (node (ref "D115") (pin "1") (pinfunction "A_1") (pintype "passive"))
      (node (ref "D131") (pin "1") (pinfunction "A_1") (pintype "passive"))
      (node (ref "D147") (pin "1") (pinfunction "A_1") (pintype "passive"))
      (node (ref "D163") (pin "1") (pinfunction "A_1") (pintype "passive"))
      (node (ref "D179") (pin "1") (pinfunction "A_1") (pintype "passive"))
      (node (ref "D19") (pin "1") (pinfunction "A_1") (pintype "passive"))
      (node (ref "D195") (pin "1") (pinfunction "A_1") (pintype "passive"))
      (node (ref "D211") (pin "1") (pinfunction "A_1") (pintype "passive"))
      (node (ref "D227") (pin "1") (pinfunction "A_1") (pintype "passive"))
      (node (ref "D243") (pin "1") (pinfunction "A_1") (pintype "passive"))
      (node (ref "D259") (pin "1") (pinfunction "A_1") (pintype "passive"))
      (node (ref "D275") (pin "1") (pinfunction "A_1") (pintype "passive"))
      (node (ref "D3") (pin "1") (pinfunction "A_1") (pintype "passive"))
      (node (ref "D35") (pin "1") (pinfunction "A_1") (pintype "passive"))
      (node (ref "D51") (pin "1") (pinfunction "A_1") (pintype "passive"))
      (node (ref "D67") (pin "1") (pinfunction "A_1") (pintype "passive"))
      (node (ref "D83") (pin "1") (pinfunction "A_1") (pintype "passive"))
      (node (ref "D99") (pin "1") (pinfunction "A_1") (pintype "passive"))
    )
    (net (code "4") (name "/COL<3>") (class "Default")
      (node (ref "D100") (pin "1") (pinfunction "A_1") (pintype "passive"))
      (node (ref "D116") (pin "1") (pinfunction "A_1") (pintype "passive"))
      (node (ref "D132") (pin "1") (pinfunction "A_1") (pintype "passive"))
      (node (ref "D148") (pin "1") (pinfunction "A_1") (pintype "passive"))
      (node (ref "D164") (pin "1") (pinfunction "A_1") (pintype "passive"))
      (node (ref "D180") (pin "1") (pinfunction "A_1") (pintype "passive"))
      (node (ref "D196") (pin "1") (pinfunction "A_1") (pintype "passive"))
      (node (ref "D20") (pin "1") (pinfunction "A_1") (pintype "passive"))
      (node (ref "D212") (pin "1") (pinfunction "A_1") (pintype "passive"))
      (node (ref "D228") (pin "1") (pinfunction "A_1") (pintype "passive"))
      (node (ref "D244") (pin "1") (pinfunction "A_1") (pintype "passive"))
      (node (ref "D260") (pin "1") (pinfunction "A_1") (pintype "passive"))
      (node (ref "D276") (pin "1") (pinfunction "A_1") (pintype "passive"))
      (node (ref "D36") (pin "1") (pinfunction "A_1") (pintype "passive"))
      (node (ref "D4") (pin "1") (pinfunction "A_1") (pintype "passive"))
      (node (ref "D52") (pin "1") (pinfunction "A_1") (pintype "passive"))
      (node (ref "D68") (pin "1") (pinfunction "A_1") (pintype "passive"))
      (node (ref "D84") (pin "1") (pinfunction "A_1") (pintype "passive"))
    )
    (net (code "5") (name "/COL<4>") (class "Default")
      (node (ref "D101") (pin "1") (pinfunction "A_1") (pintype "passive"))
      (node (ref "D117") (pin "1") (pinfunction "A_1") (pintype "passive"))
      (node (ref "D133") (pin "1") (pinfunction "A_1") (pintype "passive"))
      (node (ref "D149") (pin "1") (pinfunction "A_1") (pintype "passive"))
      (node (ref "D165") (pin "1") (pinfunction "A_1") (pintype "passive"))
      (node (ref "D181") (pin "1") (pinfunction "A_1") (pintype "passive"))
      (node (ref "D197") (pin "1") (pinfunction "A_1") (pintype "passive"))
      (node (ref "D21") (pin "1") (pinfunction "A_1") (pintype "passive"))
      (node (ref "D213") (pin "1") (pinfunction "A_1") (pintype "passive"))
      (node (ref "D229") (pin "1") (pinfunction "A_1") (pintype "passive"))
      (node (ref "D245") (pin "1") (pinfunction "A_1") (pintype "passive"))
      (node (ref "D261") (pin "1") (pinfunction "A_1") (pintype "passive"))
      (node (ref "D277") (pin "1") (pinfunction "A_1") (pintype "passive"))
      (node (ref "D37") (pin "1") (pinfunction "A_1") (pintype "passive"))
      (node (ref "D5") (pin "1") (pinfunction "A_1") (pintype "passive"))
      (node (ref "D53") (pin "1") (pinfunction "A_1") (pintype "passive"))
      (node (ref "D69") (pin "1") (pinfunction "A_1") (pintype "passive"))
      (node (ref "D85") (pin "1") (pinfunction "A_1") (pintype "passive"))
    )
    (net (code "6") (name "/COL<5>") (class "Default")
      (node (ref "D102") (pin "1") (pinfunction "A_1") (pintype "passive"))
      (node (ref "D118") (pin "1") (pinfunction "A_1") (pintype "passive"))
      (node (ref "D134") (pin "1") (pinfunction "A_1") (pintype "passive"))
      (node (ref "D150") (pin "1") (pinfunction "A_1") (pintype "passive"))
      (node (ref "D166") (pin "1") (pinfunction "A_1") (pintype "passive"))
      (node (ref "D182") (pin "1") (pinfunction "A_1") (pintype "passive"))
      (node (ref "D198") (pin "1") (pinfunction "A_1") (pintype "passive"))
      (node (ref "D214") (pin "1") (pinfunction "A_1") (pintype "passive"))
      (node (ref "D22") (pin "1") (pinfunction "A_1") (pintype "passive"))
      (node (ref "D230") (pin "1") (pinfunction "A_1") (pintype "passive"))
      (node (ref "D246") (pin "1") (pinfunction "A_1") (pintype "passive"))
      (node (ref "D262") (pin "1") (pinfunction "A_1") (pintype "passive"))
      (node (ref "D278") (pin "1") (pinfunction "A_1") (pintype "passive"))
      (node (ref "D38") (pin "1") (pinfunction "A_1") (pintype "passive"))
      (node (ref "D54") (pin "1") (pinfunction "A_1") (pintype "passive"))
      (node (ref "D6") (pin "1") (pinfunction "A_1") (pintype "passive"))
      (node (ref "D70") (pin "1") (pinfunction "A_1") (pintype "passive"))
      (node (ref "D86") (pin "1") (pinfunction "A_1") (pintype "passive"))
    )
    (net (code "7") (name "/COL<6>") (class "Default")
      (node (ref "D103") (pin "1") (pinfunction "A_1") (pintype "passive"))
      (node (ref "D119") (pin "1") (pinfunction "A_1") (pintype "passive"))
      (node (ref "D135") (pin "1") (pinfunction "A_1") (pintype "passive"))
      (node (ref "D151") (pin "1") (pinfunction "A_1") (pintype "passive"))
      (node (ref "D167") (pin "1") (pinfunction "A_1") (pintype "passive"))
      (node (ref "D183") (pin "1") (pinfunction "A_1") (pintype "passive"))
      (node (ref "D199") (pin "1") (pinfunction "A_1") (pintype "passive"))
      (node (ref "D215") (pin "1") (pinfunction "A_1") (pintype "passive"))
      (node (ref "D23") (pin "1") (pinfunction "A_1") (pintype "passive"))
      (node (ref "D231") (pin "1") (pinfunction "A_1") (pintype "passive"))
      (node (ref "D247") (pin "1") (pinfunction "A_1") (pintype "passive"))
      (node (ref "D263") (pin "1") (pinfunction "A_1") (pintype "passive"))
      (node (ref "D279") (pin "1") (pinfunction "A_1") (pintype "passive"))
      (node (ref "D39") (pin "1") (pinfunction "A_1") (pintype "passive"))
      (node (ref "D55") (pin "1") (pinfunction "A_1") (pintype "passive"))
      (node (ref "D7") (pin "1") (pinfunction "A_1") (pintype "passive"))
      (node (ref "D71") (pin "1") (pinfunction "A_1") (pintype "passive"))
      (node (ref "D87") (pin "1") (pinfunction "A_1") (pintype "passive"))
    )
    (net (code "8") (name "/COL<7>") (class "Default")
      (node (ref "D104") (pin "1") (pinfunction "A_1") (pintype "passive"))
      (node (ref "D120") (pin "1") (pinfunction "A_1") (pintype "passive"))
      (node (ref "D136") (pin "1") (pinfunction "A_1") (pintype "passive"))
      (node (ref "D152") (pin "1") (pinfunction "A_1") (pintype "passive"))
      (node (ref "D168") (pin "1") (pinfunction "A_1") (pintype "passive"))
      (node (ref "D184") (pin "1") (pinfunction "A_1") (pintype "passive"))
      (node (ref "D200") (pin "1") (pinfunction "A_1") (pintype "passive"))
      (node (ref "D216") (pin "1") (pinfunction "A_1") (pintype "passive"))
      (node (ref "D232") (pin "1") (pinfunction "A_1") (pintype "passive"))
      (node (ref "D24") (pin "1") (pinfunction "A_1") (pintype "passive"))
      (node (ref "D248") (pin "1") (pinfunction "A_1") (pintype "passive"))
      (node (ref "D264") (pin "1") (pinfunction "A_1") (pintype "passive"))
      (node (ref "D280") (pin "1") (pinfunction "A_1") (pintype "passive"))
      (node (ref "D40") (pin "1") (pinfunction "A_1") (pintype "passive"))
      (node (ref "D56") (pin "1") (pinfunction "A_1") (pintype "passive"))
      (node (ref "D72") (pin "1") (pinfunction "A_1") (pintype "passive"))
      (node (ref "D8") (pin "1") (pinfunction "A_1") (pintype "passive"))
      (node (ref "D88") (pin "1") (pinfunction "A_1") (pintype "passive"))
    )
    (net (code "9") (name "/COL<8>") (class "Default")
      (node (ref "D105") (pin "1") (pinfunction "A_1") (pintype "passive"))
      (node (ref "D121") (pin "1") (pinfunction "A_1") (pintype "passive"))
      (node (ref "D137") (pin "1") (pinfunction "A_1") (pintype "passive"))
      (node (ref "D153") (pin "1") (pinfunction "A_1") (pintype "passive"))
      (node (ref "D169") (pin "1") (pinfunction "A_1") (pintype "passive"))
      (node (ref "D185") (pin "1") (pinfunction "A_1") (pintype "passive"))
      (node (ref "D201") (pin "1") (pinfunction "A_1") (pintype "passive"))
      (node (ref "D217") (pin "1") (pinfunction "A_1") (pintype "passive"))
      (node (ref "D233") (pin "1") (pinfunction "A_1") (pintype "passive"))
      (node (ref "D249") (pin "1") (pinfunction "A_1") (pintype "passive"))
      (node (ref "D25") (pin "1") (pinfunction "A_1") (pintype "passive"))
      (node (ref "D265") (pin "1") (pinfunction "A_1") (pintype "passive"))
      (node (ref "D281") (pin "1") (pinfunction "A_1") (pintype "passive"))
      (node (ref "D41") (pin "1") (pinfunction "A_1") (pintype "passive"))
      (node (ref "D57") (pin "1") (pinfunction "A_1") (pintype "passive"))
      (node (ref "D73") (pin "1") (pinfunction "A_1") (pintype "passive"))
      (node (ref "D89") (pin "1") (pinfunction "A_1") (pintype "passive"))
      (node (ref "D9") (pin "1") (pinfunction "A_1") (pintype "passive"))
    )
    (net (code "10") (name "/COL<9>") (class "Default")
      (node (ref "D10") (pin "1") (pinfunction "A_1") (pintype "passive"))
      (node (ref "D106") (pin "1") (pinfunction "A_1") (pintype "passive"))
      (node (ref "D122") (pin "1") (pinfunction "A_1") (pintype "passive"))
      (node (ref "D138") (pin "1") (pinfunction "A_1") (pintype "passive"))
      (node (ref "D154") (pin "1") (pinfunction "A_1") (pintype "passive"))
      (node (ref "D170") (pin "1") (pinfunction "A_1") (pintype "passive"))
      (node (ref "D186") (pin "1") (pinfunction "A_1") (pintype "passive"))
      (node (ref "D202") (pin "1") (pinfunction "A_1") (pintype "passive"))
      (node (ref "D218") (pin "1") (pinfunction "A_1") (pintype "passive"))
      (node (ref "D234") (pin "1") (pinfunction "A_1") (pintype "passive"))
      (node (ref "D250") (pin "1") (pinfunction "A_1") (pintype "passive"))
      (node (ref "D26") (pin "1") (pinfunction "A_1") (pintype "passive"))
      (node (ref "D266") (pin "1") (pinfunction "A_1") (pintype "passive"))
      (node (ref "D282") (pin "1") (pinfunction "A_1") (pintype "passive"))
      (node (ref "D42") (pin "1") (pinfunction "A_1") (pintype "passive"))
      (node (ref "D58") (pin "1") (pinfunction "A_1") (pintype "passive"))
      (node (ref "D74") (pin "1") (pinfunction "A_1") (pintype "passive"))
      (node (ref "D90") (pin "1") (pinfunction "A_1") (pintype "passive"))
    )
    (net (code "11") (name "/COL<10>") (class "Default")
      (node (ref "D107") (pin "1") (pinfunction "A_1") (pintype "passive"))
      (node (ref "D11") (pin "1") (pinfunction "A_1") (pintype "passive"))
      (node (ref "D123") (pin "1") (pinfunction "A_1") (pintype "passive"))
      (node (ref "D139") (pin "1") (pinfunction "A_1") (pintype "passive"))
      (node (ref "D155") (pin "1") (pinfunction "A_1") (pintype "passive"))
      (node (ref "D171") (pin "1") (pinfunction "A_1") (pintype "passive"))
      (node (ref "D187") (pin "1") (pinfunction "A_1") (pintype "passive"))
      (node (ref "D203") (pin "1") (pinfunction "A_1") (pintype "passive"))
      (node (ref "D219") (pin "1") (pinfunction "A_1") (pintype "passive"))
      (node (ref "D235") (pin "1") (pinfunction "A_1") (pintype "passive"))
      (node (ref "D251") (pin "1") (pinfunction "A_1") (pintype "passive"))
      (node (ref "D267") (pin "1") (pinfunction "A_1") (pintype "passive"))
      (node (ref "D27") (pin "1") (pinfunction "A_1") (pintype "passive"))
      (node (ref "D283") (pin "1") (pinfunction "A_1") (pintype "passive"))
      (node (ref "D43") (pin "1") (pinfunction "A_1") (pintype "passive"))
      (node (ref "D59") (pin "1") (pinfunction "A_1") (pintype "passive"))
      (node (ref "D75") (pin "1") (pinfunction "A_1") (pintype "passive"))
      (node (ref "D91") (pin "1") (pinfunction "A_1") (pintype "passive"))
    )
    (net (code "12") (name "/COL<11>") (class "Default")
      (node (ref "D108") (pin "1") (pinfunction "A_1") (pintype "passive"))
      (node (ref "D12") (pin "1") (pinfunction "A_1") (pintype "passive"))
      (node (ref "D124") (pin "1") (pinfunction "A_1") (pintype "passive"))
      (node (ref "D140") (pin "1") (pinfunction "A_1") (pintype "passive"))
      (node (ref "D156") (pin "1") (pinfunction "A_1") (pintype "passive"))
      (node (ref "D172") (pin "1") (pinfunction "A_1") (pintype "passive"))
      (node (ref "D188") (pin "1") (pinfunction "A_1") (pintype "passive"))
      (node (ref "D204") (pin "1") (pinfunction "A_1") (pintype "passive"))
      (node (ref "D220") (pin "1") (pinfunction "A_1") (pintype "passive"))
      (node (ref "D236") (pin "1") (pinfunction "A_1") (pintype "passive"))
      (node (ref "D252") (pin "1") (pinfunction "A_1") (pintype "passive"))
      (node (ref "D268") (pin "1") (pinfunction "A_1") (pintype "passive"))
      (node (ref "D28") (pin "1") (pinfunction "A_1") (pintype "passive"))
      (node (ref "D284") (pin "1") (pinfunction "A_1") (pintype "passive"))
      (node (ref "D44") (pin "1") (pinfunction "A_1") (pintype "passive"))
      (node (ref "D60") (pin "1") (pinfunction "A_1") (pintype "passive"))
      (node (ref "D76") (pin "1") (pinfunction "A_1") (pintype "passive"))
      (node (ref "D92") (pin "1") (pinfunction "A_1") (pintype "passive"))
    )
    (net (code "13") (name "/COL<12>") (class "Default")
      (node (ref "D109") (pin "1") (pinfunction "A_1") (pintype "passive"))
      (node (ref "D125") (pin "1") (pinfunction "A_1") (pintype "passive"))
      (node (ref "D13") (pin "1") (pinfunction "A_1") (pintype "passive"))
      (node (ref "D141") (pin "1") (pinfunction "A_1") (pintype "passive"))
      (node (ref "D157") (pin "1") (pinfunction "A_1") (pintype "passive"))
      (node (ref "D173") (pin "1") (pinfunction "A_1") (pintype "passive"))
      (node (ref "D189") (pin "1") (pinfunction "A_1") (pintype "passive"))
      (node (ref "D205") (pin "1") (pinfunction "A_1") (pintype "passive"))
      (node (ref "D221") (pin "1") (pinfunction "A_1") (pintype "passive"))
      (node (ref "D237") (pin "1") (pinfunction "A_1") (pintype "passive"))
      (node (ref "D253") (pin "1") (pinfunction "A_1") (pintype "passive"))
      (node (ref "D269") (pin "1") (pinfunction "A_1") (pintype "passive"))
      (node (ref "D285") (pin "1") (pinfunction "A_1") (pintype "passive"))
      (node (ref "D29") (pin "1") (pinfunction "A_1") (pintype "passive"))
      (node (ref "D45") (pin "1") (pinfunction "A_1") (pintype "passive"))
      (node (ref "D61") (pin "1") (pinfunction "A_1") (pintype "passive"))
      (node (ref "D77") (pin "1") (pinfunction "A_1") (pintype "passive"))
      (node (ref "D93") (pin "1") (pinfunction "A_1") (pintype "passive"))
    )
    (net (code "14") (name "/COL<13>") (class "Default")
      (node (ref "D110") (pin "1") (pinfunction "A_1") (pintype "passive"))
      (node (ref "D126") (pin "1") (pinfunction "A_1") (pintype "passive"))
      (node (ref "D14") (pin "1") (pinfunction "A_1") (pintype "passive"))
      (node (ref "D142") (pin "1") (pinfunction "A_1") (pintype "passive"))
      (node (ref "D158") (pin "1") (pinfunction "A_1") (pintype "passive"))
      (node (ref "D174") (pin "1") (pinfunction "A_1") (pintype "passive"))
      (node (ref "D190") (pin "1") (pinfunction "A_1") (pintype "passive"))
      (node (ref "D206") (pin "1") (pinfunction "A_1") (pintype "passive"))
      (node (ref "D222") (pin "1") (pinfunction "A_1") (pintype "passive"))
      (node (ref "D238") (pin "1") (pinfunction "A_1") (pintype "passive"))
      (node (ref "D254") (pin "1") (pinfunction "A_1") (pintype "passive"))
      (node (ref "D270") (pin "1") (pinfunction "A_1") (pintype "passive"))
      (node (ref "D286") (pin "1") (pinfunction "A_1") (pintype "passive"))
      (node (ref "D30") (pin "1") (pinfunction "A_1") (pintype "passive"))
      (node (ref "D46") (pin "1") (pinfunction "A_1") (pintype "passive"))
      (node (ref "D62") (pin "1") (pinfunction "A_1") (pintype "passive"))
      (node (ref "D78") (pin "1") (pinfunction "A_1") (pintype "passive"))
      (node (ref "D94") (pin "1") (pinfunction "A_1") (pintype "passive"))
    )
    (net (code "15") (name "/COL<14>") (class "Default")
      (node (ref "D111") (pin "1") (pinfunction "A_1") (pintype "passive"))
      (node (ref "D127") (pin "1") (pinfunction "A_1") (pintype "passive"))
      (node (ref "D143") (pin "1") (pinfunction "A_1") (pintype "passive"))
      (node (ref "D15") (pin "1") (pinfunction "A_1") (pintype "passive"))
      (node (ref "D159") (pin "1") (pinfunction "A_1") (pintype "passive"))
      (node (ref "D175") (pin "1") (pinfunction "A_1") (pintype "passive"))
      (node (ref "D191") (pin "1") (pinfunction "A_1") (pintype "passive"))
      (node (ref "D207") (pin "1") (pinfunction "A_1") (pintype "passive"))
      (node (ref "D223") (pin "1") (pinfunction "A_1") (pintype "passive"))
      (node (ref "D239") (pin "1") (pinfunction "A_1") (pintype "passive"))
      (node (ref "D255") (pin "1") (pinfunction "A_1") (pintype "passive"))
      (node (ref "D271") (pin "1") (pinfunction "A_1") (pintype "passive"))
      (node (ref "D287") (pin "1") (pinfunction "A_1") (pintype "passive"))
      (node (ref "D31") (pin "1") (pinfunction "A_1") (pintype "passive"))
      (node (ref "D47") (pin "1") (pinfunction "A_1") (pintype "passive"))
      (node (ref "D63") (pin "1") (pinfunction "A_1") (pintype "passive"))
      (node (ref "D79") (pin "1") (pinfunction "A_1") (pintype "passive"))
      (node (ref "D95") (pin "1") (pinfunction "A_1") (pintype "passive"))
    )
    (net (code "16") (name "/COL<15>") (class "Default")
      (node (ref "D112") (pin "1") (pinfunction "A_1") (pintype "passive"))
      (node (ref "D128") (pin "1") (pinfunction "A_1") (pintype "passive"))
      (node (ref "D144") (pin "1") (pinfunction "A_1") (pintype "passive"))
      (node (ref "D16") (pin "1") (pinfunction "A_1") (pintype "passive"))
      (node (ref "D160") (pin "1") (pinfunction "A_1") (pintype "passive"))
      (node (ref "D176") (pin "1") (pinfunction "A_1") (pintype "passive"))
      (node (ref "D192") (pin "1") (pinfunction "A_1") (pintype "passive"))
      (node (ref "D208") (pin "1") (pinfunction "A_1") (pintype "passive"))
      (node (ref "D224") (pin "1") (pinfunction "A_1") (pintype "passive"))
      (node (ref "D240") (pin "1") (pinfunction "A_1") (pintype "passive"))
      (node (ref "D256") (pin "1") (pinfunction "A_1") (pintype "passive"))
      (node (ref "D272") (pin "1") (pinfunction "A_1") (pintype "passive"))
      (node (ref "D288") (pin "1") (pinfunction "A_1") (pintype "passive"))
      (node (ref "D32") (pin "1") (pinfunction "A_1") (pintype "passive"))
      (node (ref "D48") (pin "1") (pinfunction "A_1") (pintype "passive"))
      (node (ref "D64") (pin "1") (pinfunction "A_1") (pintype "passive"))
      (node (ref "D80") (pin "1") (pinfunction "A_1") (pintype "passive"))
      (node (ref "D96") (pin "1") (pinfunction "A_1") (pintype "passive"))
    )
    (net (code "17") (name "/ROW<0>") (class "Default")
      (node (ref "D1") (pin "2") (pinfunction "K_2") (pintype "passive"))
      (node (ref "D10") (pin "2") (pinfunction "K_2") (pintype "passive"))
      (node (ref "D11") (pin "2") (pinfunction "K_2") (pintype "passive"))
      (node (ref "D12") (pin "2") (pinfunction "K_2") (pintype "passive"))
      (node (ref "D13") (pin "2") (pinfunction "K_2") (pintype "passive"))
      (node (ref "D14") (pin "2") (pinfunction "K_2") (pintype "passive"))
      (node (ref "D15") (pin "2") (pinfunction "K_2") (pintype "passive"))
      (node (ref "D16") (pin "2") (pinfunction "K_2") (pintype "passive"))
      (node (ref "D2") (pin "2") (pinfunction "K_2") (pintype "passive"))
      (node (ref "D3") (pin "2") (pinfunction "K_2") (pintype "passive"))
      (node (ref "D4") (pin "2") (pinfunction "K_2") (pintype "passive"))
      (node (ref "D5") (pin "2") (pinfunction "K_2") (pintype "passive"))
      (node (ref "D6") (pin "2") (pinfunction "K_2") (pintype "passive"))
      (node (ref "D7") (pin "2") (pinfunction "K_2") (pintype "passive"))
      (node (ref "D8") (pin "2") (pinfunction "K_2") (pintype "passive"))
      (node (ref "D9") (pin "2") (pinfunction "K_2") (pintype "passive"))
    )
    (net (code "18") (name "/ROW<1>") (class "Default")
      (node (ref "D17") (pin "2") (pinfunction "K_2") (pintype "passive"))
      (node (ref "D18") (pin "2") (pinfunction "K_2") (pintype "passive"))
      (node (ref "D19") (pin "2") (pinfunction "K_2") (pintype "passive"))
      (node (ref "D20") (pin "2") (pinfunction "K_2") (pintype "passive"))
      (node (ref "D21") (pin "2") (pinfunction "K_2") (pintype "passive"))
      (node (ref "D22") (pin "2") (pinfunction "K_2") (pintype "passive"))
      (node (ref "D23") (pin "2") (pinfunction "K_2") (pintype "passive"))
      (node (ref "D24") (pin "2") (pinfunction "K_2") (pintype "passive"))
      (node (ref "D25") (pin "2") (pinfunction "K_2") (pintype "passive"))
      (node (ref "D26") (pin "2") (pinfunction "K_2") (pintype "passive"))
      (node (ref "D27") (pin "2") (pinfunction "K_2") (pintype "passive"))
      (node (ref "D28") (pin "2") (pinfunction "K_2") (pintype "passive"))
      (node (ref "D29") (pin "2") (pinfunction "K_2") (pintype "passive"))
      (node (ref "D30") (pin "2") (pinfunction "K_2") (pintype "passive"))
      (node (ref "D31") (pin "2") (pinfunction "K_2") (pintype "passive"))
      (node (ref "D32") (pin "2") (pinfunction "K_2") (pintype "passive"))
    )
    (net (code "19") (name "/ROW<2>") (class "Default")
      (node (ref "D33") (pin "2") (pinfunction "K_2") (pintype "passive"))
      (node (ref "D34") (pin "2") (pinfunction "K_2") (pintype "passive"))
      (node (ref "D35") (pin "2") (pinfunction "K_2") (pintype "passive"))
      (node (ref "D36") (pin "2") (pinfunction "K_2") (pintype "passive"))
      (node (ref "D37") (pin "2") (pinfunction "K_2") (pintype "passive"))
      (node (ref "D38") (pin "2") (pinfunction "K_2") (pintype "passive"))
      (node (ref "D39") (pin "2") (pinfunction "K_2") (pintype "passive"))
      (node (ref "D40") (pin "2") (pinfunction "K_2") (pintype "passive"))
      (node (ref "D41") (pin "2") (pinfunction "K_2") (pintype "passive"))
      (node (ref "D42") (pin "2") (pinfunction "K_2") (pintype "passive"))
      (node (ref "D43") (pin "2") (pinfunction "K_2") (pintype "passive"))
      (node (ref "D44") (pin "2") (pinfunction "K_2") (pintype "passive"))
      (node (ref "D45") (pin "2") (pinfunction "K_2") (pintype "passive"))
      (node (ref "D46") (pin "2") (pinfunction "K_2") (pintype "passive"))
      (node (ref "D47") (pin "2") (pinfunction "K_2") (pintype "passive"))
      (node (ref "D48") (pin "2") (pinfunction "K_2") (pintype "passive"))
    )
    (net (code "20") (name "/ROW<3>") (class "Default")
      (node (ref "D49") (pin "2") (pinfunction "K_2") (pintype "passive"))
      (node (ref "D50") (pin "2") (pinfunction "K_2") (pintype "passive"))
      (node (ref "D51") (pin "2") (pinfunction "K_2") (pintype "passive"))
      (node (ref "D52") (pin "2") (pinfunction "K_2") (pintype "passive"))
      (node (ref "D53") (pin "2") (pinfunction "K_2") (pintype "passive"))
      (node (ref "D54") (pin "2") (pinfunction "K_2") (pintype "passive"))
      (node (ref "D55") (pin "2") (pinfunction "K_2") (pintype "passive"))
      (node (ref "D56") (pin "2") (pinfunction "K_2") (pintype "passive"))
      (node (ref "D57") (pin "2") (pinfunction "K_2") (pintype "passive"))
      (node (ref "D58") (pin "2") (pinfunction "K_2") (pintype "passive"))
      (node (ref "D59") (pin "2") (pinfunction "K_2") (pintype "passive"))
      (node (ref "D60") (pin "2") (pinfunction "K_2") (pintype "passive"))
      (node (ref "D61") (pin "2") (pinfunction "K_2") (pintype "passive"))
      (node (ref "D62") (pin "2") (pinfunction "K_2") (pintype "passive"))
      (node (ref "D63") (pin "2") (pinfunction "K_2") (pintype "passive"))
      (node (ref "D64") (pin "2") (pinfunction "K_2") (pintype "passive"))
    )
    (net (code "21") (name "/ROW<4>") (class "Default")
      (node (ref "D65") (pin "2") (pinfunction "K_2") (pintype "passive"))
      (node (ref "D66") (pin "2") (pinfunction "K_2") (pintype "passive"))
      (node (ref "D67") (pin "2") (pinfunction "K_2") (pintype "passive"))
      (node (ref "D68") (pin "2") (pinfunction "K_2") (pintype "passive"))
      (node (ref "D69") (pin "2") (pinfunction "K_2") (pintype "passive"))
      (node (ref "D70") (pin "2") (pinfunction "K_2") (pintype "passive"))
      (node (ref "D71") (pin "2") (pinfunction "K_2") (pintype "passive"))
      (node (ref "D72") (pin "2") (pinfunction "K_2") (pintype "passive"))
      (node (ref "D73") (pin "2") (pinfunction "K_2") (pintype "passive"))
      (node (ref "D74") (pin "2") (pinfunction "K_2") (pintype "passive"))
      (node (ref "D75") (pin "2") (pinfunction "K_2") (pintype "passive"))
      (node (ref "D76") (pin "2") (pinfunction "K_2") (pintype "passive"))
      (node (ref "D77") (pin "2") (pinfunction "K_2") (pintype "passive"))
      (node (ref "D78") (pin "2") (pinfunction "K_2") (pintype "passive"))
      (node (ref "D79") (pin "2") (pinfunction "K_2") (pintype "passive"))
      (node (ref "D80") (pin "2") (pinfunction "K_2") (pintype "passive"))
    )
    (net (code "22") (name "/ROW<5>") (class "Default")
      (node (ref "D81") (pin "2") (pinfunction "K_2") (pintype "passive"))
      (node (ref "D82") (pin "2") (pinfunction "K_2") (pintype "passive"))
      (node (ref "D83") (pin "2") (pinfunction "K_2") (pintype "passive"))
      (node (ref "D84") (pin "2") (pinfunction "K_2") (pintype "passive"))
      (node (ref "D85") (pin "2") (pinfunction "K_2") (pintype "passive"))
      (node (ref "D86") (pin "2") (pinfunction "K_2") (pintype "passive"))
      (node (ref "D87") (pin "2") (pinfunction "K_2") (pintype "passive"))
      (node (ref "D88") (pin "2") (pinfunction "K_2") (pintype "passive"))
      (node (ref "D89") (pin "2") (pinfunction "K_2") (pintype "passive"))
      (node (ref "D90") (pin "2") (pinfunction "K_2") (pintype "passive"))
      (node (ref "D91") (pin "2") (pinfunction "K_2") (pintype "passive"))
      (node (ref "D92") (pin "2") (pinfunction "K_2") (pintype "passive"))
      (node (ref "D93") (pin "2") (pinfunction "K_2") (pintype "passive"))
      (node (ref "D94") (pin "2") (pinfunction "K_2") (pintype "passive"))
      (node (ref "D95") (pin "2") (pinfunction "K_2") (pintype "passive"))
      (node (ref "D96") (pin "2") (pinfunction "K_2") (pintype "passive"))
    )
    (net (code "23") (name "/ROW<6>") (class "Default")
      (node (ref "D100") (pin "2") (pinfunction "K_2") (pintype "passive"))
      (node (ref "D101") (pin "2") (pinfunction "K_2") (pintype "passive"))
      (node (ref "D102") (pin "2") (pinfunction "K_2") (pintype "passive"))
      (node (ref "D103") (pin "2") (pinfunction "K_2") (pintype "passive"))
      (node (ref "D104") (pin "2") (pinfunction "K_2") (pintype "passive"))
      (node (ref "D105") (pin "2") (pinfunction "K_2") (pintype "passive"))
      (node (ref "D106") (pin "2") (pinfunction "K_2") (pintype "passive"))
      (node (ref "D107") (pin "2") (pinfunction "K_2") (pintype "passive"))
      (node (ref "D108") (pin "2") (pinfunction "K_2") (pintype "passive"))
      (node (ref "D109") (pin "2") (pinfunction "K_2") (pintype "passive"))
      (node (ref "D110") (pin "2") (pinfunction "K_2") (pintype "passive"))
      (node (ref "D111") (pin "2") (pinfunction "K_2") (pintype "passive"))
      (node (ref "D112") (pin "2") (pinfunction "K_2") (pintype "passive"))
      (node (ref "D97") (pin "2") (pinfunction "K_2") (pintype "passive"))
      (node (ref "D98") (pin "2") (pinfunction "K_2") (pintype "passive"))
      (node (ref "D99") (pin "2") (pinfunction "K_2") (pintype "passive"))
    )
    (net (code "24") (name "/ROW<7>") (class "Default")
      (node (ref "D113") (pin "2") (pinfunction "K_2") (pintype "passive"))
      (node (ref "D114") (pin "2") (pinfunction "K_2") (pintype "passive"))
      (node (ref "D115") (pin "2") (pinfunction "K_2") (pintype "passive"))
      (node (ref "D116") (pin "2") (pinfunction "K_2") (pintype "passive"))
      (node (ref "D117") (pin "2") (pinfunction "K_2") (pintype "passive"))
      (node (ref "D118") (pin "2") (pinfunction "K_2") (pintype "passive"))
      (node (ref "D119") (pin "2") (pinfunction "K_2") (pintype "passive"))
      (node (ref "D120") (pin "2") (pinfunction "K_2") (pintype "passive"))
      (node (ref "D121") (pin "2") (pinfunction "K_2") (pintype "passive"))
      (node (ref "D122") (pin "2") (pinfunction "K_2") (pintype "passive"))
      (node (ref "D123") (pin "2") (pinfunction "K_2") (pintype "passive"))
      (node (ref "D124") (pin "2") (pinfunction "K_2") (pintype "passive"))
      (node (ref "D125") (pin "2") (pinfunction "K_2") (pintype "passive"))
      (node (ref "D126") (pin "2") (pinfunction "K_2") (pintype "passive"))
      (node (ref "D127") (pin "2") (pinfunction "K_2") (pintype "passive"))
      (node (ref "D128") (pin "2") (pinfunction "K_2") (pintype "passive"))
    )
    (net (code "25") (name "/ROW<8>") (class "Default")
      (node (ref "D129") (pin "2") (pinfunction "K_2") (pintype "passive"))
      (node (ref "D130") (pin "2") (pinfunction "K_2") (pintype "passive"))
      (node (ref "D131") (pin "2") (pinfunction "K_2") (pintype "passive"))
      (node (ref "D132") (pin "2") (pinfunction "K_2") (pintype "passive"))
      (node (ref "D133") (pin "2") (pinfunction "K_2") (pintype "passive"))
      (node (ref "D134") (pin "2") (pinfunction "K_2") (pintype "passive"))
      (node (ref "D135") (pin "2") (pinfunction "K_2") (pintype "passive"))
      (node (ref "D136") (pin "2") (pinfunction "K_2") (pintype "passive"))
      (node (ref "D137") (pin "2") (pinfunction "K_2") (pintype "passive"))
      (node (ref "D138") (pin "2") (pinfunction "K_2") (pintype "passive"))
      (node (ref "D139") (pin "2") (pinfunction "K_2") (pintype "passive"))
      (node (ref "D140") (pin "2") (pinfunction "K_2") (pintype "passive"))
      (node (ref "D141") (pin "2") (pinfunction "K_2") (pintype "passive"))
      (node (ref "D142") (pin "2") (pinfunction "K_2") (pintype "passive"))
      (node (ref "D143") (pin "2") (pinfunction "K_2") (pintype "passive"))
      (node (ref "D144") (pin "2") (pinfunction "K_2") (pintype "passive"))
    )
    (net (code "26") (name "/ROW<9>") (class "Default")
      (node (ref "D145") (pin "2") (pinfunction "K_2") (pintype "passive"))
      (node (ref "D146") (pin "2") (pinfunction "K_2") (pintype "passive"))
      (node (ref "D147") (pin "2") (pinfunction "K_2") (pintype "passive"))
      (node (ref "D148") (pin "2") (pinfunction "K_2") (pintype "passive"))
      (node (ref "D149") (pin "2") (pinfunction "K_2") (pintype "passive"))
      (node (ref "D150") (pin "2") (pinfunction "K_2") (pintype "passive"))
      (node (ref "D151") (pin "2") (pinfunction "K_2") (pintype "passive"))
      (node (ref "D152") (pin "2") (pinfunction "K_2") (pintype "passive"))
      (node (ref "D153") (pin "2") (pinfunction "K_2") (pintype "passive"))
      (node (ref "D154") (pin "2") (pinfunction "K_2") (pintype "passive"))
      (node (ref "D155") (pin "2") (pinfunction "K_2") (pintype "passive"))
      (node (ref "D156") (pin "2") (pinfunction "K_2") (pintype "passive"))
      (node (ref "D157") (pin "2") (pinfunction "K_2") (pintype "passive"))
      (node (ref "D158") (pin "2") (pinfunction "K_2") (pintype "passive"))
      (node (ref "D159") (pin "2") (pinfunction "K_2") (pintype "passive"))
      (node (ref "D160") (pin "2") (pinfunction "K_2") (pintype "passive"))
    )
    (net (code "27") (name "/ROW<10>") (class "Default")
      (node (ref "D161") (pin "2") (pinfunction "K_2") (pintype "passive"))
      (node (ref "D162") (pin "2") (pinfunction "K_2") (pintype "passive"))
      (node (ref "D163") (pin "2") (pinfunction "K_2") (pintype "passive"))
      (node (ref "D164") (pin "2") (pinfunction "K_2") (pintype "passive"))
      (node (ref "D165") (pin "2") (pinfunction "K_2") (pintype "passive"))
      (node (ref "D166") (pin "2") (pinfunction "K_2") (pintype "passive"))
      (node (ref "D167") (pin "2") (pinfunction "K_2") (pintype "passive"))
      (node (ref "D168") (pin "2") (pinfunction "K_2") (pintype "passive"))
      (node (ref "D169") (pin "2") (pinfunction "K_2") (pintype "passive"))
      (node (ref "D170") (pin "2") (pinfunction "K_2") (pintype "passive"))
      (node (ref "D171") (pin "2") (pinfunction "K_2") (pintype "passive"))
      (node (ref "D172") (pin "2") (pinfunction "K_2") (pintype "passive"))
      (node (ref "D173") (pin "2") (pinfunction "K_2") (pintype "passive"))
      (node (ref "D174") (pin "2") (pinfunction "K_2") (pintype "passive"))
      (node (ref "D175") (pin "2") (pinfunction "K_2") (pintype "passive"))
      (node (ref "D176") (pin "2") (pinfunction "K_2") (pintype "passive"))
    )
    (net (code "28") (name "/ROW<11>") (class "Default")
      (node (ref "D177") (pin "2") (pinfunction "K_2") (pintype "passive"))
      (node (ref "D178") (pin "2") (pinfunction "K_2") (pintype "passive"))
      (node (ref "D179") (pin "2") (pinfunction "K_2") (pintype "passive"))
      (node (ref "D180") (pin "2") (pinfunction "K_2") (pintype "passive"))
      (node (ref "D181") (pin "2") (pinfunction "K_2") (pintype "passive"))
      (node (ref "D182") (pin "2") (pinfunction "K_2") (pintype "passive"))
      (node (ref "D183") (pin "2") (pinfunction "K_2") (pintype "passive"))
      (node (ref "D184") (pin "2") (pinfunction "K_2") (pintype "passive"))
      (node (ref "D185") (pin "2") (pinfunction "K_2") (pintype "passive"))
      (node (ref "D186") (pin "2") (pinfunction "K_2") (pintype "passive"))
      (node (ref "D187") (pin "2") (pinfunction "K_2") (pintype "passive"))
      (node (ref "D188") (pin "2") (pinfunction "K_2") (pintype "passive"))
      (node (ref "D189") (pin "2") (pinfunction "K_2") (pintype "passive"))
      (node (ref "D190") (pin "2") (pinfunction "K_2") (pintype "passive"))
      (node (ref "D191") (pin "2") (pinfunction "K_2") (pintype "passive"))
      (node (ref "D192") (pin "2") (pinfunction "K_2") (pintype "passive"))
    )
    (net (code "29") (name "/ROW<12>") (class "Default")
      (node (ref "D193") (pin "2") (pinfunction "K_2") (pintype "passive"))
      (node (ref "D194") (pin "2") (pinfunction "K_2") (pintype "passive"))
      (node (ref "D195") (pin "2") (pinfunction "K_2") (pintype "passive"))
      (node (ref "D196") (pin "2") (pinfunction "K_2") (pintype "passive"))
      (node (ref "D197") (pin "2") (pinfunction "K_2") (pintype "passive"))
      (node (ref "D198") (pin "2") (pinfunction "K_2") (pintype "passive"))
      (node (ref "D199") (pin "2") (pinfunction "K_2") (pintype "passive"))
      (node (ref "D200") (pin "2") (pinfunction "K_2") (pintype "passive"))
      (node (ref "D201") (pin "2") (pinfunction "K_2") (pintype "passive"))
      (node (ref "D202") (pin "2") (pinfunction "K_2") (pintype "passive"))
      (node (ref "D203") (pin "2") (pinfunction "K_2") (pintype "passive"))
      (node (ref "D204") (pin "2") (pinfunction "K_2") (pintype "passive"))
      (node (ref "D205") (pin "2") (pinfunction "K_2") (pintype "passive"))
      (node (ref "D206") (pin "2") (pinfunction "K_2") (pintype "passive"))
      (node (ref "D207") (pin "2") (pinfunction "K_2") (pintype "passive"))
      (node (ref "D208") (pin "2") (pinfunction "K_2") (pintype "passive"))
    )
    (net (code "30") (name "/ROW<13>") (class "Default")
      (node (ref "D209") (pin "2") (pinfunction "K_2") (pintype "passive"))
      (node (ref "D210") (pin "2") (pinfunction "K_2") (pintype "passive"))
      (node (ref "D211") (pin "2") (pinfunction "K_2") (pintype "passive"))
      (node (ref "D212") (pin "2") (pinfunction "K_2") (pintype "passive"))
      (node (ref "D213") (pin "2") (pinfunction "K_2") (pintype "passive"))
      (node (ref "D214") (pin "2") (pinfunction "K_2") (pintype "passive"))
      (node (ref "D215") (pin "2") (pinfunction "K_2") (pintype "passive"))
      (node (ref "D216") (pin "2") (pinfunction "K_2") (pintype "passive"))
      (node (ref "D217") (pin "2") (pinfunction "K_2") (pintype "passive"))
      (node (ref "D218") (pin "2") (pinfunction "K_2") (pintype "passive"))
      (node (ref "D219") (pin "2") (pinfunction "K_2") (pintype "passive"))
      (node (ref "D220") (pin "2") (pinfunction "K_2") (pintype "passive"))
      (node (ref "D221") (pin "2") (pinfunction "K_2") (pintype "passive"))
      (node (ref "D222") (pin "2") (pinfunction "K_2") (pintype "passive"))
      (node (ref "D223") (pin "2") (pinfunction "K_2") (pintype "passive"))
      (node (ref "D224") (pin "2") (pinfunction "K_2") (pintype "passive"))
    )
    (net (code "31") (name "/ROW<14>") (class "Default")
      (node (ref "D225") (pin "2") (pinfunction "K_2") (pintype "passive"))
      (node (ref "D226") (pin "2") (pinfunction "K_2") (pintype "passive"))
      (node (ref "D227") (pin "2") (pinfunction "K_2") (pintype "passive"))
      (node (ref "D228") (pin "2") (pinfunction "K_2") (pintype "passive"))
      (node (ref "D229") (pin "2") (pinfunction "K_2") (pintype "passive"))
      (node (ref "D230") (pin "2") (pinfunction "K_2") (pintype "passive"))
      (node (ref "D231") (pin "2") (pinfunction "K_2") (pintype "passive"))
      (node (ref "D232") (pin "2") (pinfunction "K_2") (pintype "passive"))
      (node (ref "D233") (pin "2") (pinfunction "K_2") (pintype "passive"))
      (node (ref "D234") (pin "2") (pinfunction "K_2") (pintype "passive"))
      (node (ref "D235") (pin "2") (pinfunction "K_2") (pintype "passive"))
      (node (ref "D236") (pin "2") (pinfunction "K_2") (pintype "passive"))
      (node (ref "D237") (pin "2") (pinfunction "K_2") (pintype "passive"))
      (node (ref "D238") (pin "2") (pinfunction "K_2") (pintype "passive"))
      (node (ref "D239") (pin "2") (pinfunction "K_2") (pintype "passive"))
      (node (ref "D240") (pin "2") (pinfunction "K_2") (pintype "passive"))
    )
    (net (code "32") (name "/ROW<15>") (class "Default")
      (node (ref "D241") (pin "2") (pinfunction "K_2") (pintype "passive"))
      (node (ref "D242") (pin "2") (pinfunction "K_2") (pintype "passive"))
      (node (ref "D243") (pin "2") (pinfunction "K_2") (pintype "passive"))
      (node (ref "D244") (pin "2") (pinfunction "K_2") (pintype "passive"))
      (node (ref "D245") (pin "2") (pinfunction "K_2") (pintype "passive"))
      (node (ref "D246") (pin "2") (pinfunction "K_2") (pintype "passive"))
      (node (ref "D247") (pin "2") (pinfunction "K_2") (pintype "passive"))
      (node (ref "D248") (pin "2") (pinfunction "K_2") (pintype "passive"))
      (node (ref "D249") (pin "2") (pinfunction "K_2") (pintype "passive"))
      (node (ref "D250") (pin "2") (pinfunction "K_2") (pintype "passive"))
      (node (ref "D251") (pin "2") (pinfunction "K_2") (pintype "passive"))
      (node (ref "D252") (pin "2") (pinfunction "K_2") (pintype "passive"))
      (node (ref "D253") (pin "2") (pinfunction "K_2") (pintype "passive"))
      (node (ref "D254") (pin "2") (pinfunction "K_2") (pintype "passive"))
      (node (ref "D255") (pin "2") (pinfunction "K_2") (pintype "passive"))
      (node (ref "D256") (pin "2") (pinfunction "K_2") (pintype "passive"))
    )
    (net (code "33") (name "/ROW<16>") (class "Default")
      (node (ref "D257") (pin "2") (pinfunction "K_2") (pintype "passive"))
      (node (ref "D258") (pin "2") (pinfunction "K_2") (pintype "passive"))
      (node (ref "D259") (pin "2") (pinfunction "K_2") (pintype "passive"))
      (node (ref "D260") (pin "2") (pinfunction "K_2") (pintype "passive"))
      (node (ref "D261") (pin "2") (pinfunction "K_2") (pintype "passive"))
      (node (ref "D262") (pin "2") (pinfunction "K_2") (pintype "passive"))
      (node (ref "D263") (pin "2") (pinfunction "K_2") (pintype "passive"))
      (node (ref "D264") (pin "2") (pinfunction "K_2") (pintype "passive"))
      (node (ref "D265") (pin "2") (pinfunction "K_2") (pintype "passive"))
      (node (ref "D266") (pin "2") (pinfunction "K_2") (pintype "passive"))
      (node (ref "D267") (pin "2") (pinfunction "K_2") (pintype "passive"))
      (node (ref "D268") (pin "2") (pinfunction "K_2") (pintype "passive"))
      (node (ref "D269") (pin "2") (pinfunction "K_2") (pintype "passive"))
      (node (ref "D270") (pin "2") (pinfunction "K_2") (pintype "passive"))
      (node (ref "D271") (pin "2") (pinfunction "K_2") (pintype "passive"))
      (node (ref "D272") (pin "2") (pinfunction "K_2") (pintype "passive"))
    )
    (net (code "34") (name "/ROW<17>") (class "Default")
      (node (ref "D273") (pin "2") (pinfunction "K_2") (pintype "passive"))
      (node (ref "D274") (pin "2") (pinfunction "K_2") (pintype "passive"))
      (node (ref "D275") (pin "2") (pinfunction "K_2") (pintype "passive"))
      (node (ref "D276") (pin "2") (pinfunction "K_2") (pintype "passive"))
      (node (ref "D277") (pin "2") (pinfunction "K_2") (pintype "passive"))
      (node (ref "D278") (pin "2") (pinfunction "K_2") (pintype "passive"))
      (node (ref "D279") (pin "2") (pinfunction "K_2") (pintype "passive"))
      (node (ref "D280") (pin "2") (pinfunction "K_2") (pintype "passive"))
      (node (ref "D281") (pin "2") (pinfunction "K_2") (pintype "passive"))
      (node (ref "D282") (pin "2") (pinfunction "K_2") (pintype "passive"))
      (node (ref "D283") (pin "2") (pinfunction "K_2") (pintype "passive"))
      (node (ref "D284") (pin "2") (pinfunction "K_2") (pintype "passive"))
      (node (ref "D285") (pin "2") (pinfunction "K_2") (pintype "passive"))
      (node (ref "D286") (pin "2") (pinfunction "K_2") (pintype "passive"))
      (node (ref "D287") (pin "2") (pinfunction "K_2") (pintype "passive"))
      (node (ref "D288") (pin "2") (pinfunction "K_2") (pintype "passive"))
    )
  )
)
